# ProPrj__Buck-Boost__V1_2_2026-08-30.net
KiCad netlist of a schematic drawn in EasyEDA Pro
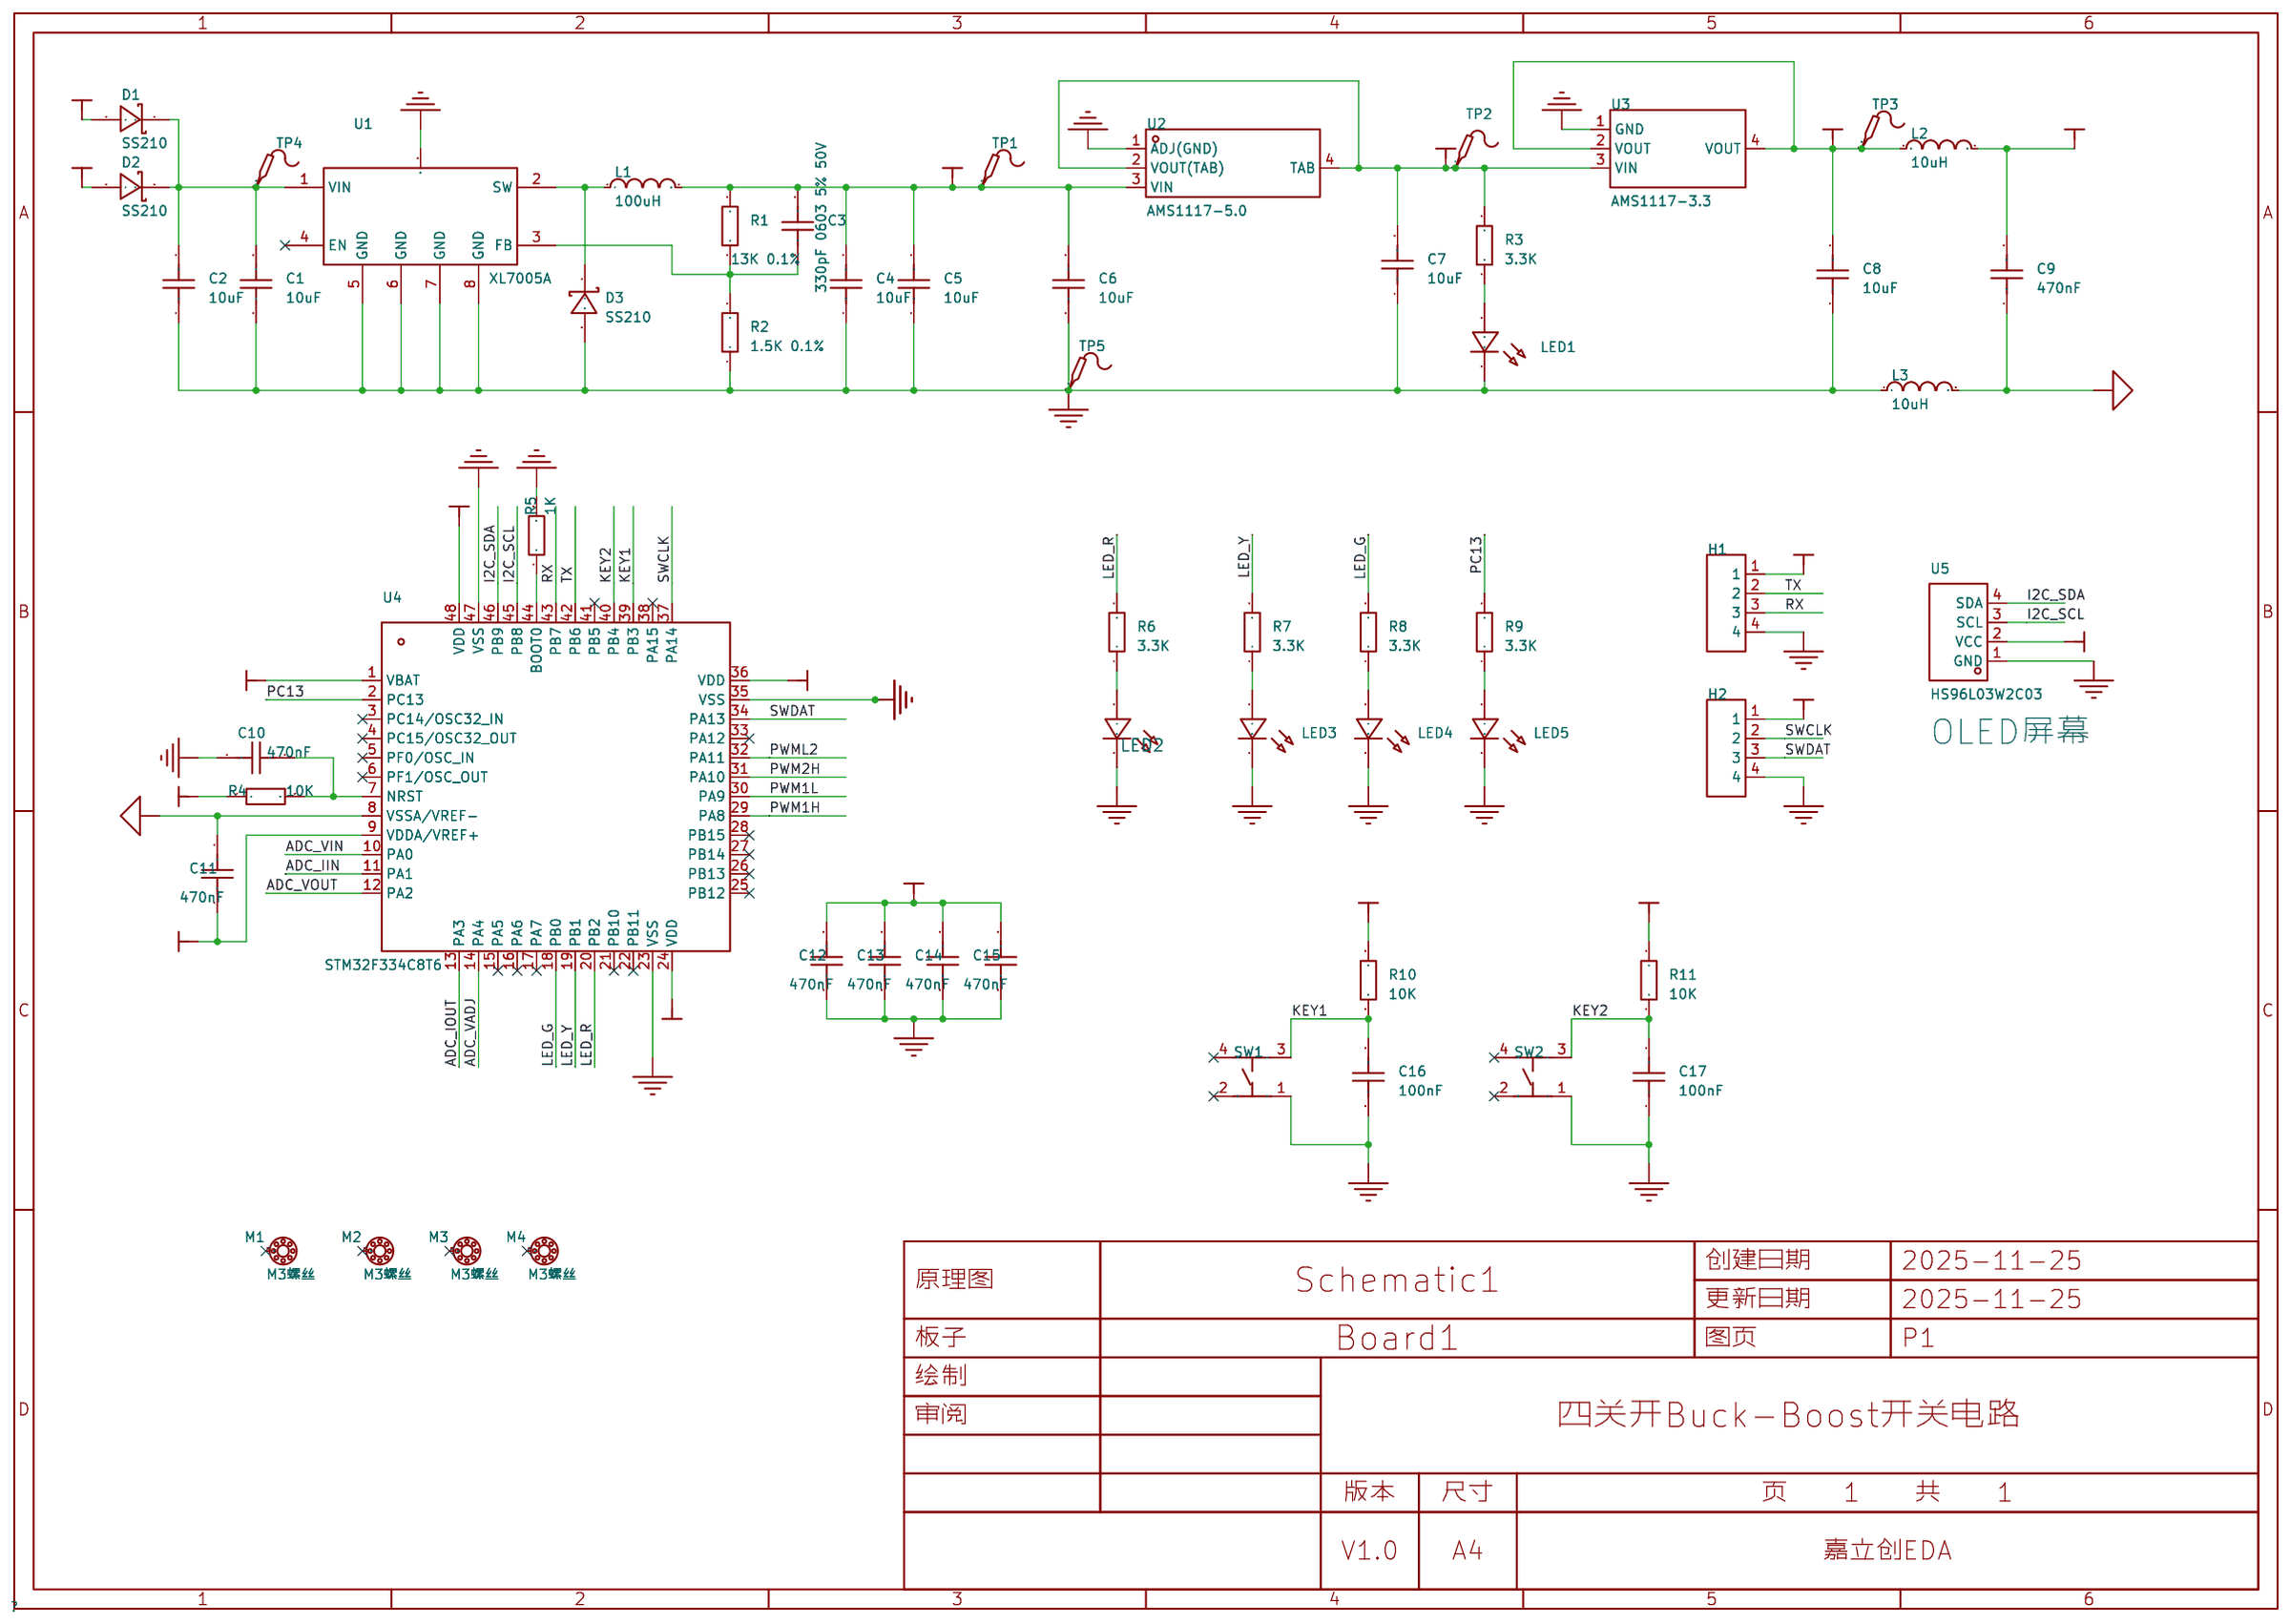
[diagram p0: 辅助电源&主控芯片]
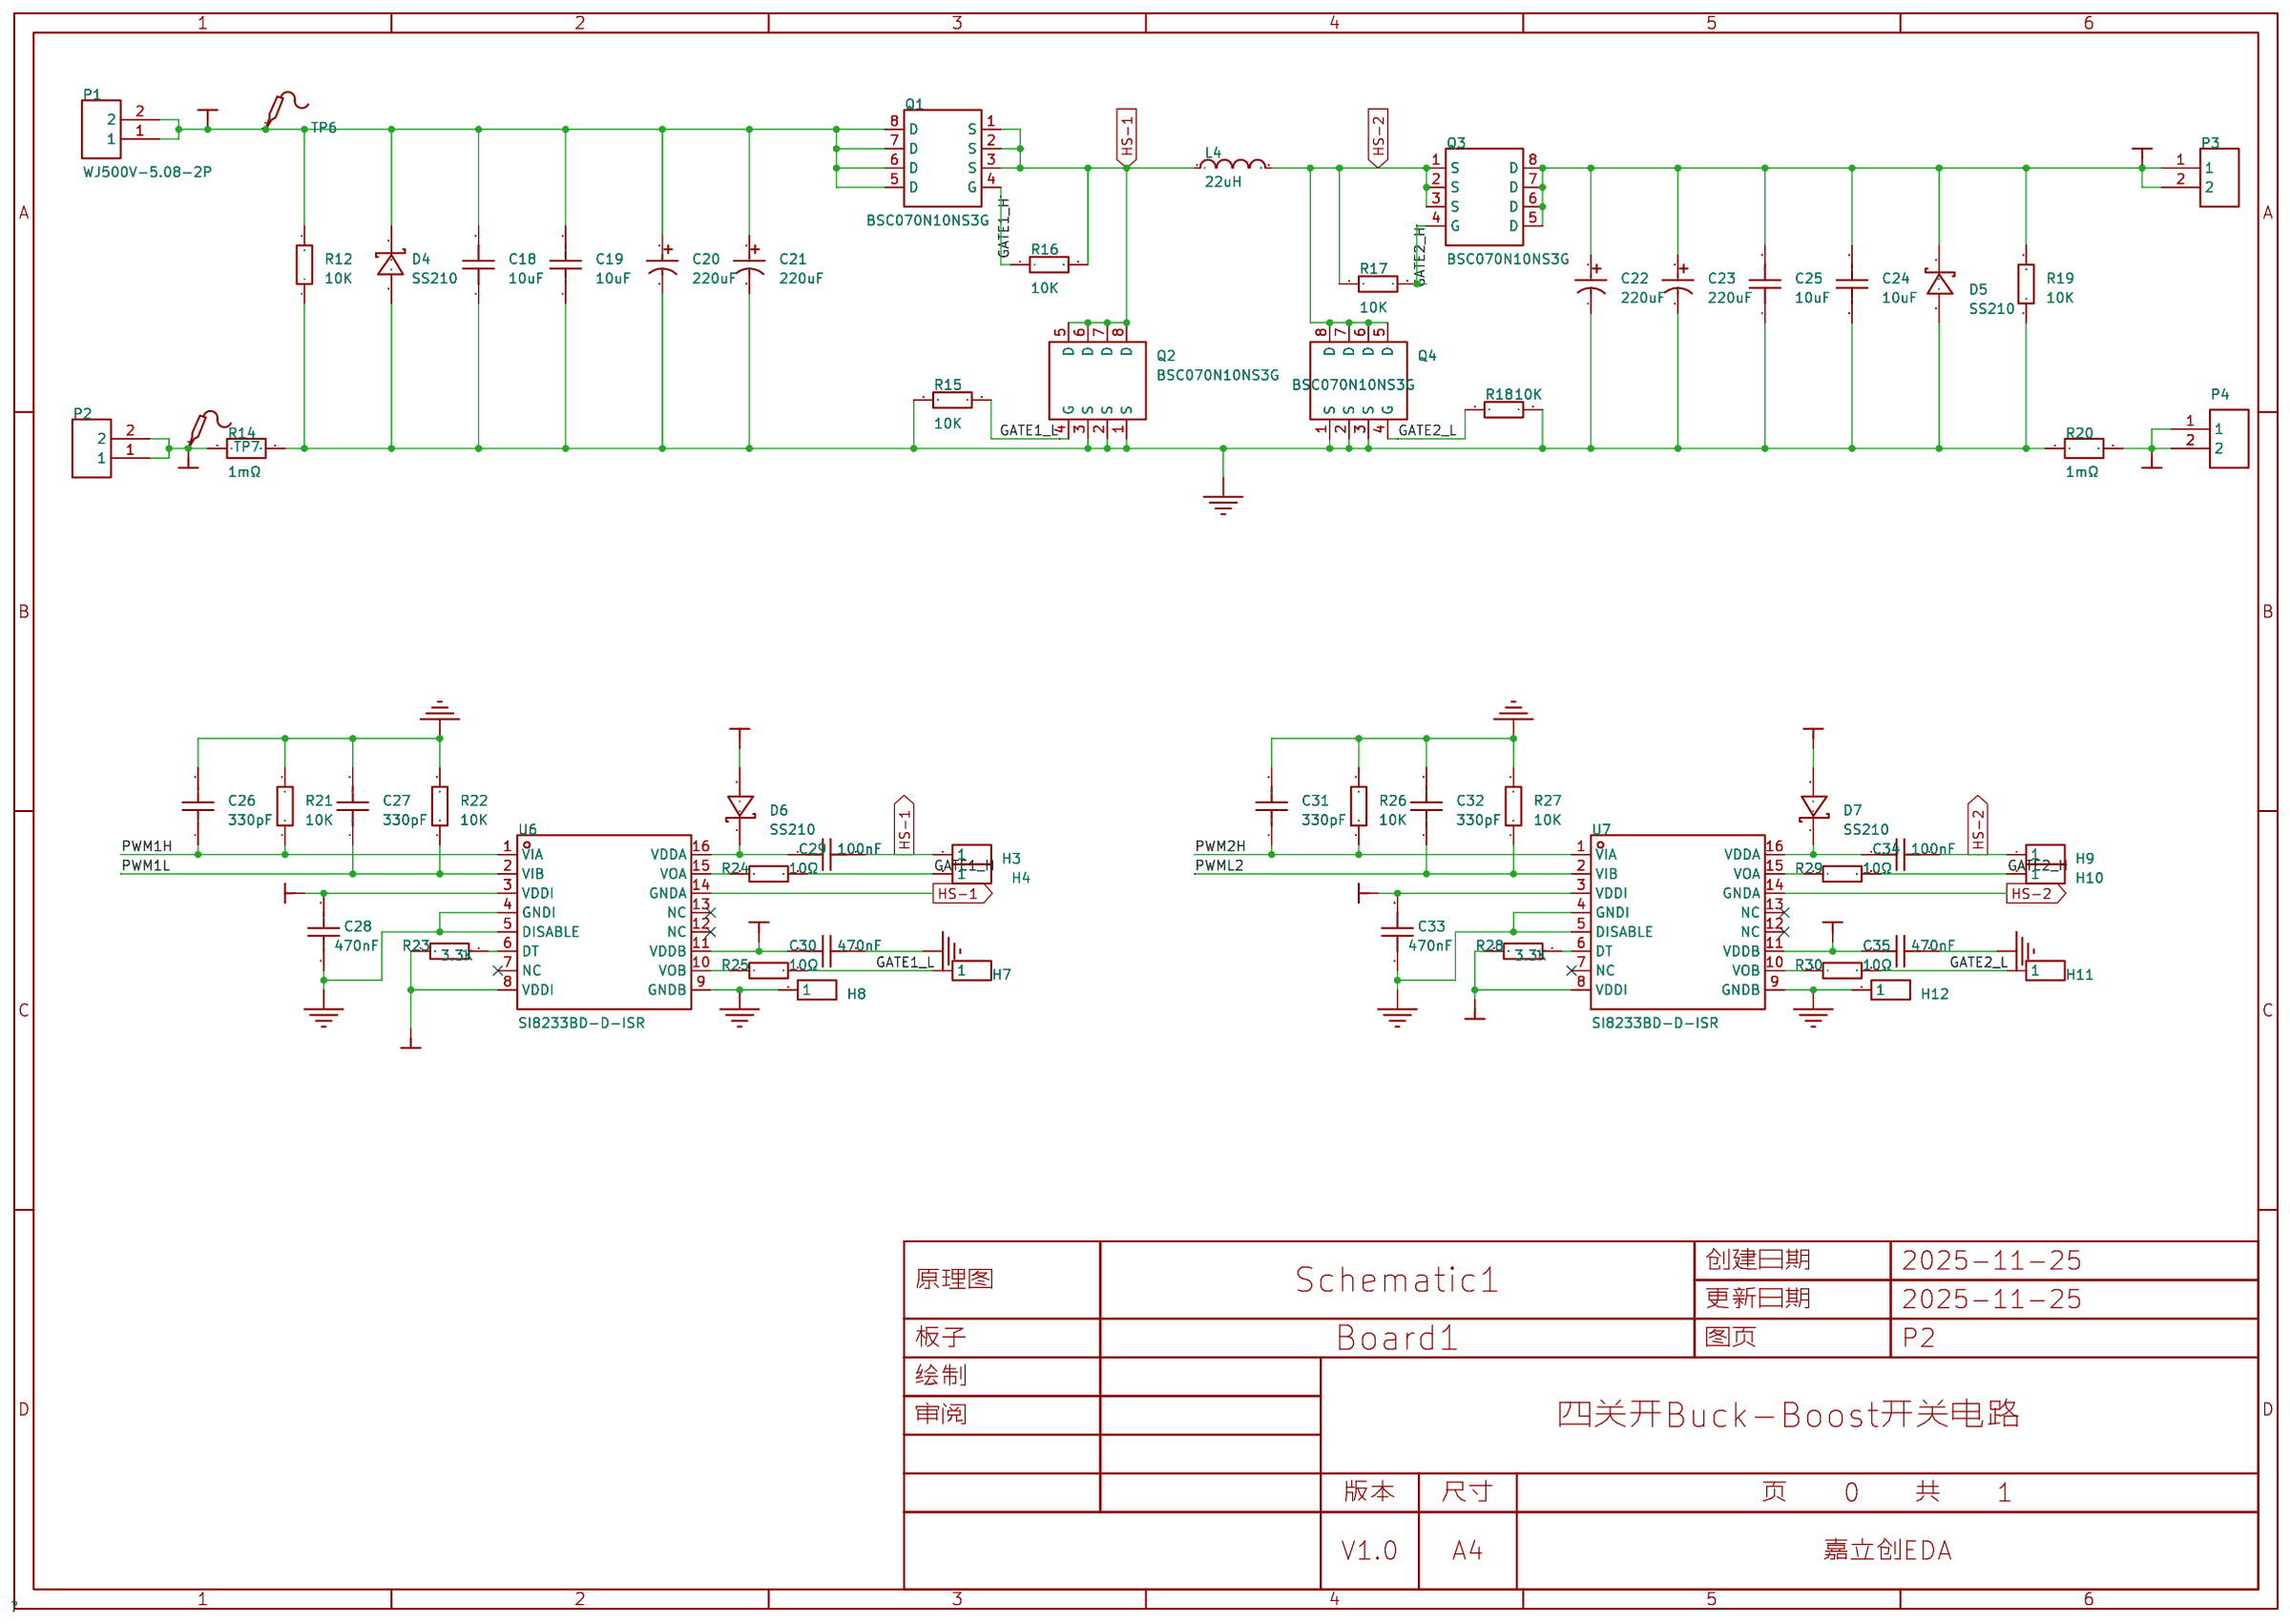
[diagram p1: 主功率&驱动]
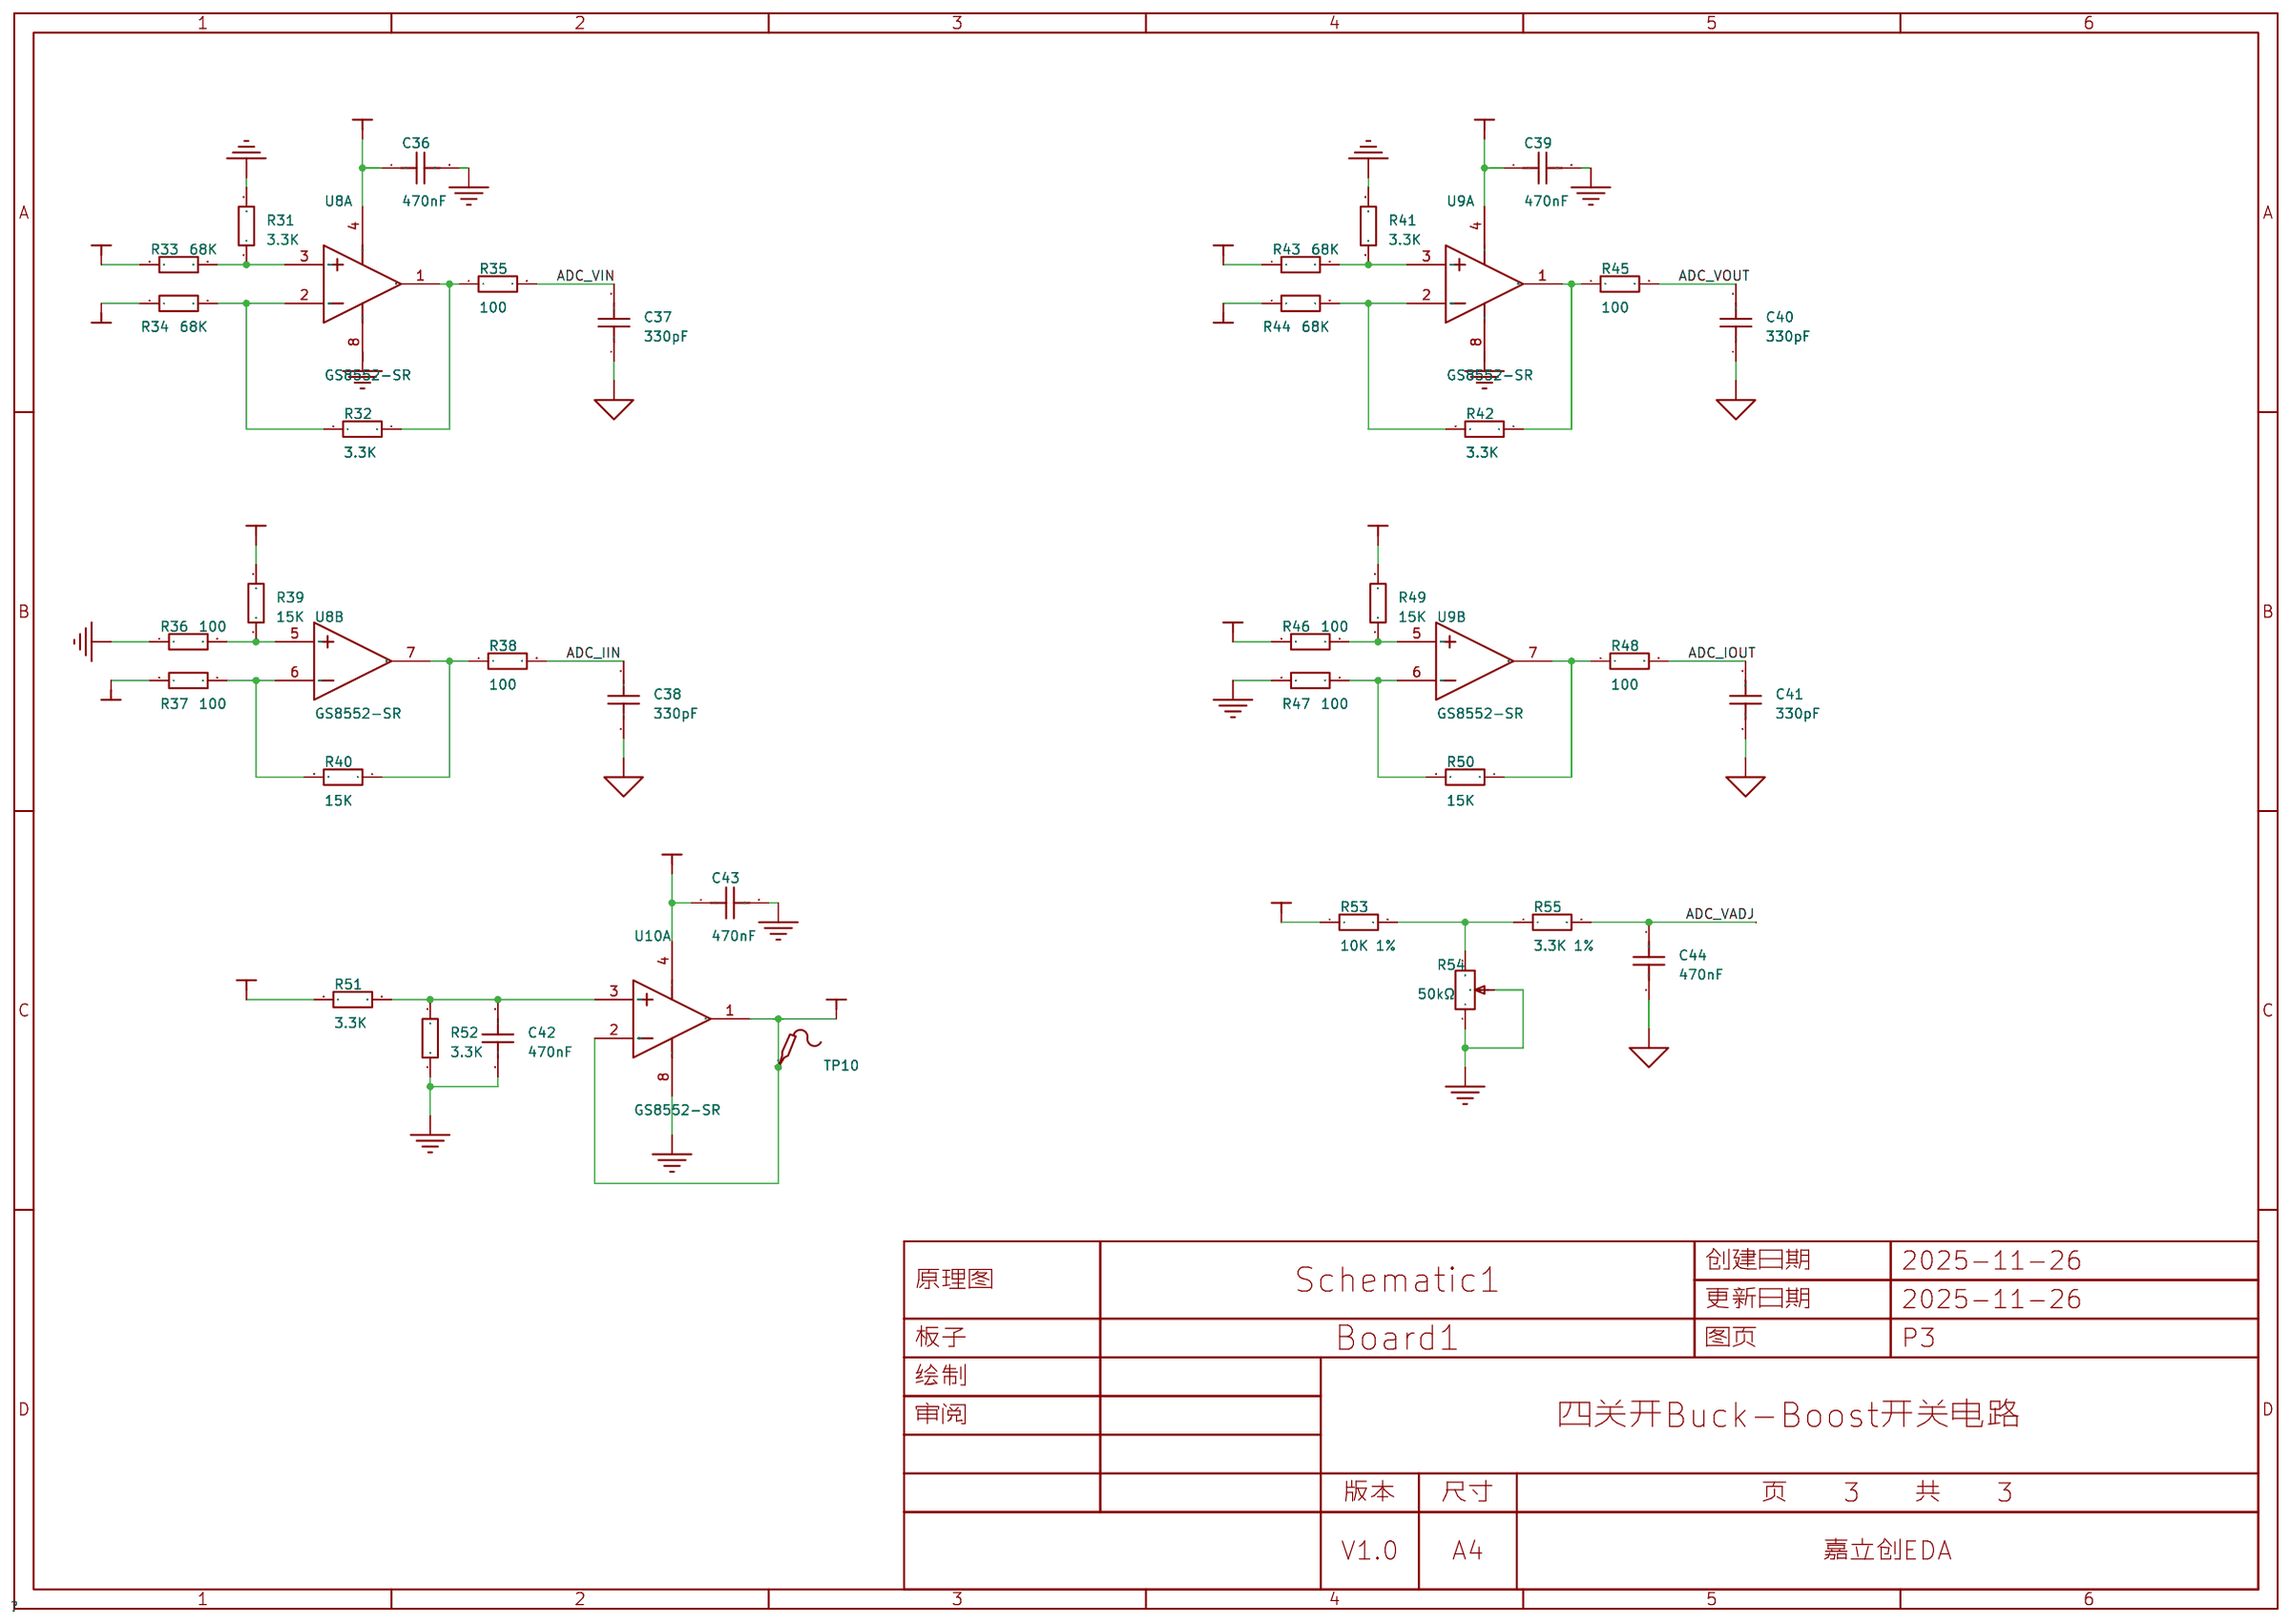
[diagram p2: 信号处理]

(export (version "E")
  (design (tool "Eeschema 10.0.6"))
  (components
    (comp (ref "C1")
      (value "10uF")
      (footprint "easyedapro:C0805")
      (libsource (lib "easyedapro") (part "Capacitance"))
    )
    (comp (ref "C2")
      (value "10uF")
      (footprint "easyedapro:C0805")
      (libsource (lib "easyedapro") (part "Capacitance"))
    )
    (comp (ref "C3")
      (value "330pF 0603 5% 50V")
      (footprint "easyedapro:C0805")
      (libsource (lib "easyedapro") (part "Capacitance"))
    )
    (comp (ref "C4")
      (value "10uF")
      (footprint "easyedapro:C0805")
      (libsource (lib "easyedapro") (part "Capacitance"))
    )
    (comp (ref "C5")
      (value "10uF")
      (footprint "easyedapro:C0805")
      (libsource (lib "easyedapro") (part "Capacitance"))
    )
    (comp (ref "C6")
      (value "10uF")
      (footprint "easyedapro:C0805")
      (libsource (lib "easyedapro") (part "Capacitance"))
    )
    (comp (ref "C7")
      (value "10uF")
      (footprint "easyedapro:C0805")
      (libsource (lib "easyedapro") (part "Capacitance"))
    )
    (comp (ref "C8")
      (value "10uF")
      (footprint "easyedapro:C0805")
      (libsource (lib "easyedapro") (part "Capacitance"))
    )
    (comp (ref "C9")
      (value "470nF")
      (footprint "easyedapro:C0805")
      (libsource (lib "easyedapro") (part "Capacitance"))
    )
    (comp (ref "C10")
      (value "470nF")
      (footprint "easyedapro:C0805")
      (libsource (lib "easyedapro") (part "Capacitance"))
    )
    (comp (ref "C11")
      (value "470nF")
      (footprint "easyedapro:C0805")
      (libsource (lib "easyedapro") (part "Capacitance"))
    )
    (comp (ref "C12")
      (value "470nF")
      (footprint "easyedapro:C0805")
      (libsource (lib "easyedapro") (part "Capacitance"))
    )
    (comp (ref "C13")
      (value "470nF")
      (footprint "easyedapro:C0805")
      (libsource (lib "easyedapro") (part "Capacitance"))
    )
    (comp (ref "C14")
      (value "470nF")
      (footprint "easyedapro:C0805")
      (libsource (lib "easyedapro") (part "Capacitance"))
    )
    (comp (ref "C15")
      (value "470nF")
      (footprint "easyedapro:C0805")
      (libsource (lib "easyedapro") (part "Capacitance"))
    )
    (comp (ref "C16")
      (value "100nF")
      (footprint "easyedapro:C0805")
      (libsource (lib "easyedapro") (part "Capacitance"))
    )
    (comp (ref "C17")
      (value "100nF")
      (footprint "easyedapro:C0805")
      (libsource (lib "easyedapro") (part "Capacitance"))
    )
    (comp (ref "D1")
      (value "SS210")
      (footprint "easyedapro:SMA_L4.4-W2.8-LS5.4-RD")
      (description "正向压降(Vf):850mV@1A;直流反向耐压(Vr):100V;整流电流:2A;")
      (fields (field (name "Manufacturer") "BORN(伯恩半导体)"))
      (libsource (lib "easyedapro") (part "SS210_C306853"))
    )
    (comp (ref "D2")
      (value "SS210")
      (footprint "easyedapro:SMA_L4.4-W2.8-LS5.4-RD")
      (description "正向压降(Vf):850mV@1A;直流反向耐压(Vr):100V;整流电流:2A;")
      (fields (field (name "Manufacturer") "BORN(伯恩半导体)"))
      (libsource (lib "easyedapro") (part "SS210_C306853"))
    )
    (comp (ref "D3")
      (value "SS210")
      (footprint "easyedapro:SMA_L4.4-W2.8-LS5.4-RD")
      (description "正向压降(Vf):850mV@1A;直流反向耐压(Vr):100V;整流电流:2A;")
      (fields (field (name "Manufacturer") "BORN(伯恩半导体)"))
      (libsource (lib "easyedapro") (part "SS210_C306853"))
    )
    (comp (ref "H1")
      (value "~")
      (footprint "easyedapro:HDR-TH_4P-P2.54-V-M")
      (libsource (lib "easyedapro") (part "PZ254V-11-04P"))
    )
    (comp (ref "H2")
      (value "~")
      (footprint "easyedapro:HDR-TH_4P-P2.54-V-M")
      (libsource (lib "easyedapro") (part "PZ254V-11-04P"))
    )
    (comp (ref "L1")
      (value "100uH")
      (footprint "easyedapro:IND-SMD_L6.0-W6.0_FNR60XXS")
      (description "电感值:100uH;精度:±20%;额定电流:880mA;饱和电流(Isat):1A;类型:磁胶屏蔽绕线合金电感;")
      (fields (field (name "Manufacturer Part") "FNR6045S101MT") (field (name "Manufacturer") "cjiang(长江微电)"))
      (libsource (lib "easyedapro") (part "FNR6045S101MT"))
    )
    (comp (ref "L2")
      (value "10uH")
      (footprint "easyedapro:L0603")
      (libsource (lib "easyedapro") (part "SDFL1608S100KTF"))
    )
    (comp (ref "L3")
      (value "10uH")
      (footprint "easyedapro:L0603")
      (libsource (lib "easyedapro") (part "SDFL1608S100KTF"))
    )
    (comp (ref "LED1")
      (value "~")
      (footprint "easyedapro:LED_0603")
      (libsource (lib "easyedapro") (part "LED_G"))
    )
    (comp (ref "LED2")
      (value "~")
      (footprint "easyedapro:LED_0603")
      (libsource (lib "easyedapro") (part "LED_R"))
    )
    (comp (ref "LED3")
      (value "~")
      (footprint "easyedapro:LED_0603")
      (libsource (lib "easyedapro") (part "LED_B"))
    )
    (comp (ref "LED4")
      (value "~")
      (footprint "easyedapro:LED_0603")
      (libsource (lib "easyedapro") (part "LED_G"))
    )
    (comp (ref "LED5")
      (value "~")
      (footprint "easyedapro:LED_0603")
      (libsource (lib "easyedapro") (part "LED_G"))
    )
    (comp (ref "M1") (value "M3螺丝") (footprint "easyedapro:螺钉孔") (libsource (lib "easyedapro") (part "M3螺丝")))
    (comp (ref "M2") (value "M3螺丝") (footprint "easyedapro:螺钉孔") (libsource (lib "easyedapro") (part "M3螺丝")))
    (comp (ref "M3") (value "M3螺丝") (footprint "easyedapro:螺钉孔") (libsource (lib "easyedapro") (part "M3螺丝")))
    (comp (ref "M4") (value "M3螺丝") (footprint "easyedapro:螺钉孔") (libsource (lib "easyedapro") (part "M3螺丝")))
    (comp (ref "R1")
      (value "13K 0.1%")
      (footprint "easyedapro:R0603")
      (libsource (lib "easyedapro") (part "电阻"))
    )
    (comp (ref "R2")
      (value "1.5K 0.1%")
      (footprint "easyedapro:R0603")
      (libsource (lib "easyedapro") (part "电阻"))
    )
    (comp (ref "R3") (value "3.3K") (footprint "easyedapro:R0603") (libsource (lib "easyedapro") (part "电阻")))
    (comp (ref "R4") (value "10K") (footprint "easyedapro:R0603") (libsource (lib "easyedapro") (part "电阻")))
    (comp (ref "R5") (value "1K") (footprint "easyedapro:R0603") (libsource (lib "easyedapro") (part "电阻")))
    (comp (ref "R6") (value "3.3K") (footprint "easyedapro:R0603") (libsource (lib "easyedapro") (part "电阻")))
    (comp (ref "R7") (value "3.3K") (footprint "easyedapro:R0603") (libsource (lib "easyedapro") (part "电阻")))
    (comp (ref "R8") (value "3.3K") (footprint "easyedapro:R0603") (libsource (lib "easyedapro") (part "电阻")))
    (comp (ref "R9") (value "3.3K") (footprint "easyedapro:R0603") (libsource (lib "easyedapro") (part "电阻")))
    (comp (ref "R10") (value "10K") (footprint "easyedapro:R0603") (libsource (lib "easyedapro") (part "电阻")))
    (comp (ref "R11") (value "10K") (footprint "easyedapro:R0603") (libsource (lib "easyedapro") (part "电阻")))
    (comp (ref "SW1")
      (value "KH-6X6X5H-STM")
      (footprint "easyedapro:SW-SMD_4P-L6.0-W6.0-P4.50-LS9.0_H5.0")
      (fields (field (name "Manufacturer") "kinghelm(金航标)"))
      (libsource (lib "easyedapro") (part "KH-6X6X5H-STM"))
    )
    (comp (ref "SW2")
      (value "KH-6X6X5H-STM")
      (footprint "easyedapro:SW-SMD_4P-L6.0-W6.0-P4.50-LS9.0_H5.0")
      (fields (field (name "Manufacturer") "kinghelm(金航标)"))
      (libsource (lib "easyedapro") (part "KH-6X6X5H-STM"))
    )
    (comp (ref "TP1")
      (value "~")
      (footprint "easyedapro:Test-Point-0.5mm")
      (description "Test Point 测试点")
      (libsource (lib "easyedapro") (part "Test-Point"))
    )
    (comp (ref "TP2")
      (value "~")
      (footprint "easyedapro:Test-Point-0.5mm")
      (description "Test Point 测试点")
      (libsource (lib "easyedapro") (part "Test-Point"))
    )
    (comp (ref "TP3")
      (value "~")
      (footprint "easyedapro:Test-Point-0.5mm")
      (description "Test Point 测试点")
      (libsource (lib "easyedapro") (part "Test-Point"))
    )
    (comp (ref "TP4")
      (value "~")
      (footprint "easyedapro:Test-Point-0.5mm")
      (description "Test Point 测试点")
      (libsource (lib "easyedapro") (part "Test-Point"))
    )
    (comp (ref "TP5")
      (value "~")
      (footprint "easyedapro:Test-Point-0.5mm")
      (description "Test Point 测试点")
      (libsource (lib "easyedapro") (part "Test-Point"))
    )
    (comp (ref "U1")
      (value "XL7005A")
      (footprint "easyedapro:SOIC-8_L4.9-W3.9-P1.27-LS6.0-BL-EP3.1-1")
      (description "功能类型:降压型;工作电压:5V~80V;输出电压:1.25V~20V;输出电流:400mA;输出类型:可调;")
      (fields (field (name "Manufacturer") "XLSEMI(芯龙)"))
      (libsource (lib "easyedapro") (part "XL7005A"))
    )
    (comp (ref "U2")
      (value "AMS1117-5.0")
      (footprint "easyedapro:SOT-223_L6.7-W3.5-P2.30-BR")
      (description "输出类型:固定;工作电压:18V;输出电压:5V;输出电流:1A;电源纹波抑制比(PSRR):60dB@(120Hz);输出极性:正极;")
      (fields (field (name "Manufacturer") "UMW(友台半导体)"))
      (libsource (lib "easyedapro") (part "AMS1117-5.0_C347223"))
    )
    (comp (ref "U3")
      (value "AMS1117-3.3")
      (footprint "easyedapro:SOT-223-3_L6.5-W3.4-P2.30-LS7.0-BR")
      (description "输出类型:固定;工作电压:16V;输出电压:3.3V;输出电流:1A;电源纹波抑制比(PSRR):72dB@(120Hz);输出极性:正极;")
      (fields (field (name "Manufacturer") "AMS"))
      (libsource (lib "easyedapro") (part "AMS1117-3.3"))
    )
    (comp (ref "U4")
      (value "STM32F334C8T6")
      (footprint "easyedapro:LQFP-48_L7.0-W7.0-P0.50-LS9.0-BL")
      (description "CPU内核:ARM-M4;CPU最大主频:72MHz;应用领域:-;")
      (fields (field (name "Manufacturer") "ST(意法半导体)"))
      (libsource (lib "easyedapro") (part "STM32F334C8T6"))
    )
    (comp (ref "U5")
      (value "HS96L03W2C03")
      (footprint "easyedapro:OLED-TH_L27.8-W27.2-P2.54_C9900033791")
      (fields (field (name "Manufacturer") "HS(汉昇)"))
      (libsource (lib "easyedapro") (part "HS96L03W2C03"))
    )
    (comp (ref "C18")
      (value "10uF")
      (footprint "easyedapro:C0805")
      (libsource (lib "easyedapro") (part "Capacitance"))
    )
    (comp (ref "C19")
      (value "10uF")
      (footprint "easyedapro:C0805")
      (libsource (lib "easyedapro") (part "Capacitance"))
    )
    (comp (ref "C20")
      (value "220uF")
      (footprint "easyedapro:CAP-TH_BD10.0-P5.00-D1.0-FD")
      (fields
        (field (name "Manufacturer Part") "GR227M063G17RR0VL4FP0")
        (field (name "Manufacturer") "Chengx(承兴)")
      )
      (libsource (lib "easyedapro") (part "220uf/63V"))
    )
    (comp (ref "C21")
      (value "220uF")
      (footprint "easyedapro:CAP-TH_BD10.0-P5.00-D1.0-FD")
      (fields
        (field (name "Manufacturer Part") "GR227M063G17RR0VL4FP0")
        (field (name "Manufacturer") "Chengx(承兴)")
      )
      (libsource (lib "easyedapro") (part "220uf/63V"))
    )
    (comp (ref "C22")
      (value "220uF")
      (footprint "easyedapro:CAP-TH_BD10.0-P5.00-D1.0-FD")
      (fields
        (field (name "Manufacturer Part") "GR227M063G17RR0VL4FP0")
        (field (name "Manufacturer") "Chengx(承兴)")
      )
      (libsource (lib "easyedapro") (part "220uf/63V"))
    )
    (comp (ref "C23")
      (value "220uF")
      (footprint "easyedapro:CAP-TH_BD10.0-P5.00-D1.0-FD")
      (fields
        (field (name "Manufacturer Part") "GR227M063G17RR0VL4FP0")
        (field (name "Manufacturer") "Chengx(承兴)")
      )
      (libsource (lib "easyedapro") (part "220uf/63V"))
    )
    (comp (ref "C24")
      (value "10uF")
      (footprint "easyedapro:C0805")
      (libsource (lib "easyedapro") (part "Capacitance"))
    )
    (comp (ref "C25")
      (value "10uF")
      (footprint "easyedapro:C0805")
      (libsource (lib "easyedapro") (part "Capacitance"))
    )
    (comp (ref "C26")
      (value "330pF")
      (footprint "easyedapro:C0805")
      (libsource (lib "easyedapro") (part "Capacitance"))
    )
    (comp (ref "C27")
      (value "330pF")
      (footprint "easyedapro:C0805")
      (libsource (lib "easyedapro") (part "Capacitance"))
    )
    (comp (ref "C28")
      (value "470nF")
      (footprint "easyedapro:C0805")
      (libsource (lib "easyedapro") (part "Capacitance"))
    )
    (comp (ref "C29")
      (value "100nF")
      (footprint "easyedapro:C0805")
      (libsource (lib "easyedapro") (part "Capacitance"))
    )
    (comp (ref "C30")
      (value "470nF")
      (footprint "easyedapro:C0805")
      (libsource (lib "easyedapro") (part "Capacitance"))
    )
    (comp (ref "C31")
      (value "330pF")
      (footprint "easyedapro:C0805")
      (libsource (lib "easyedapro") (part "Capacitance"))
    )
    (comp (ref "C32")
      (value "330pF")
      (footprint "easyedapro:C0805")
      (libsource (lib "easyedapro") (part "Capacitance"))
    )
    (comp (ref "C33")
      (value "470nF")
      (footprint "easyedapro:C0805")
      (libsource (lib "easyedapro") (part "Capacitance"))
    )
    (comp (ref "C34")
      (value "100nF")
      (footprint "easyedapro:C0805")
      (libsource (lib "easyedapro") (part "Capacitance"))
    )
    (comp (ref "C35")
      (value "470nF")
      (footprint "easyedapro:C0805")
      (libsource (lib "easyedapro") (part "Capacitance"))
    )
    (comp (ref "D4")
      (value "SS210")
      (footprint "easyedapro:SMA_L4.4-W2.8-LS5.4-RD")
      (description "正向压降(Vf):850mV@1A;直流反向耐压(Vr):100V;整流电流:2A;")
      (fields (field (name "Manufacturer") "BORN(伯恩半导体)"))
      (libsource (lib "easyedapro") (part "SS210_C306853"))
    )
    (comp (ref "D5")
      (value "SS210")
      (footprint "easyedapro:SMA_L4.4-W2.8-LS5.4-RD")
      (description "正向压降(Vf):850mV@1A;直流反向耐压(Vr):100V;整流电流:2A;")
      (fields (field (name "Manufacturer") "BORN(伯恩半导体)"))
      (libsource (lib "easyedapro") (part "SS210_C306853"))
    )
    (comp (ref "D6")
      (value "SS210")
      (footprint "easyedapro:SMA_L4.4-W2.8-LS5.4-RD")
      (description "正向压降(Vf):850mV@1A;直流反向耐压(Vr):100V;整流电流:2A;")
      (fields (field (name "Manufacturer") "BORN(伯恩半导体)"))
      (libsource (lib "easyedapro") (part "SS210_C306853"))
    )
    (comp (ref "D7")
      (value "SS210")
      (footprint "easyedapro:SMA_L4.4-W2.8-LS5.4-RD")
      (description "正向压降(Vf):850mV@1A;直流反向耐压(Vr):100V;整流电流:2A;")
      (fields (field (name "Manufacturer") "BORN(伯恩半导体)"))
      (libsource (lib "easyedapro") (part "SS210_C306853"))
    )
    (comp (ref "H3")
      (value "~")
      (footprint "easyedapro:HDR-TH_1P-V-M_XKB_X4611WV-01I-C28D40")
      (libsource (lib "easyedapro") (part "HDR_1x1"))
    )
    (comp (ref "H4")
      (value "~")
      (footprint "easyedapro:HDR-TH_1P-V-M_XKB_X4611WV-01I-C28D40")
      (libsource (lib "easyedapro") (part "HDR_1x1"))
    )
    (comp (ref "H7")
      (value "~")
      (footprint "easyedapro:HDR-TH_1P-V-M_XKB_X4611WV-01I-C28D40")
      (libsource (lib "easyedapro") (part "HDR_1x1"))
    )
    (comp (ref "H8")
      (value "~")
      (footprint "easyedapro:HDR-TH_1P-V-M_XKB_X4611WV-01I-C28D40")
      (libsource (lib "easyedapro") (part "HDR_1x1"))
    )
    (comp (ref "H9")
      (value "~")
      (footprint "easyedapro:HDR-TH_1P-V-M_XKB_X4611WV-01I-C28D40")
      (libsource (lib "easyedapro") (part "HDR_1x1"))
    )
    (comp (ref "H10")
      (value "~")
      (footprint "easyedapro:HDR-TH_1P-V-M_XKB_X4611WV-01I-C28D40")
      (libsource (lib "easyedapro") (part "HDR_1x1"))
    )
    (comp (ref "H11")
      (value "~")
      (footprint "easyedapro:HDR-TH_1P-V-M_XKB_X4611WV-01I-C28D40")
      (libsource (lib "easyedapro") (part "HDR_1x1"))
    )
    (comp (ref "H12")
      (value "~")
      (footprint "easyedapro:HDR-TH_1P-V-M_XKB_X4611WV-01I-C28D40")
      (libsource (lib "easyedapro") (part "HDR_1x1"))
    )
    (comp (ref "L4")
      (value "22uH")
      (footprint "easyedapro:IND-SMD_L17.5-W17.0_YXMAC1770")
      (fields
        (field (name "Manufacturer Part") "TMPA1707SP-220MN-D")
        (field (name "Manufacturer") "TAI-TECH(台庆)")
      )
      (libsource (lib "easyedapro") (part "TMPA1707SP-220MN-D"))
    )
    (comp (ref "P1")
      (value "WJ500V-5.08-2P")
      (footprint "easyedapro:CONN-TH_2P-P5.00_WJ500V-5.08-2P")
      (fields (field (name "Manufacturer") "KANGNEX(康奈克斯电气)"))
      (libsource (lib "easyedapro") (part "WJ500V-5.08-2P-14-00A"))
    )
    (comp (ref "P2")
      (value "WJ500V-5.08-2P")
      (footprint "easyedapro:CONN-TH_2P-P5.00_WJ500V-5.08-2P")
      (fields (field (name "Manufacturer") "KANGNEX(康奈克斯电气)"))
      (libsource (lib "easyedapro") (part "WJ500V-5.08-2P-14-00A"))
    )
    (comp (ref "P3")
      (value "WJ500V-5.08-2P")
      (footprint "easyedapro:CONN-TH_2P-P5.00_WJ500V-5.08-2P")
      (fields (field (name "Manufacturer") "KANGNEX(康奈克斯电气)"))
      (libsource (lib "easyedapro") (part "WJ500V-5.08-2P-14-00A"))
    )
    (comp (ref "P4")
      (value "WJ500V-5.08-2P")
      (footprint "easyedapro:CONN-TH_2P-P5.00_WJ500V-5.08-2P")
      (fields (field (name "Manufacturer") "KANGNEX(康奈克斯电气)"))
      (libsource (lib "easyedapro") (part "WJ500V-5.08-2P-14-00A"))
    )
    (comp (ref "Q1")
      (value "BSC070N10NS3G")
      (footprint "easyedapro:PG-TDSON-8_L5.0-W6.0-P1.27-BL-EP")
      (fields (field (name "Manufacturer") "Infineon(英飞凌)"))
      (libsource (lib "easyedapro") (part "BSC070N10NS3G"))
    )
    (comp (ref "Q2")
      (value "BSC070N10NS3G")
      (footprint "easyedapro:PG-TDSON-8_L5.0-W6.0-P1.27-BL-EP")
      (fields (field (name "Manufacturer") "Infineon(英飞凌)"))
      (libsource (lib "easyedapro") (part "BSC070N10NS3G"))
    )
    (comp (ref "Q3")
      (value "BSC070N10NS3G")
      (footprint "easyedapro:PG-TDSON-8_L5.0-W6.0-P1.27-BL-EP")
      (fields (field (name "Manufacturer") "Infineon(英飞凌)"))
      (libsource (lib "easyedapro") (part "BSC070N10NS3G"))
    )
    (comp (ref "Q4")
      (value "BSC070N10NS3G")
      (footprint "easyedapro:PG-TDSON-8_L5.0-W6.0-P1.27-BL-EP")
      (fields (field (name "Manufacturer") "Infineon(英飞凌)"))
      (libsource (lib "easyedapro") (part "BSC070N10NS3G"))
    )
    (comp (ref "R12") (value "10K") (footprint "easyedapro:R0603") (libsource (lib "easyedapro") (part "电阻")))
    (comp (ref "R14")
      (value "1mΩ")
      (footprint "easyedapro:RES-SMD_L6.3-W3.2_R2512")
      (fields (field (name "Manufacturer Part") "RE2512F3R001") (field (name "Manufacturer") "JIERR(捷而瑞)"))
      (libsource (lib "easyedapro") (part "RE2512F3R001"))
    )
    (comp (ref "R15") (value "10K") (footprint "easyedapro:R0603") (libsource (lib "easyedapro") (part "电阻")))
    (comp (ref "R16") (value "10K") (footprint "easyedapro:R0603") (libsource (lib "easyedapro") (part "电阻")))
    (comp (ref "R17") (value "10K") (footprint "easyedapro:R0603") (libsource (lib "easyedapro") (part "电阻")))
    (comp (ref "R18") (value "10K") (footprint "easyedapro:R0603") (libsource (lib "easyedapro") (part "电阻")))
    (comp (ref "R19") (value "10K") (footprint "easyedapro:R0603") (libsource (lib "easyedapro") (part "电阻")))
    (comp (ref "R20")
      (value "1mΩ")
      (footprint "easyedapro:RES-SMD_L6.3-W3.2_R2512")
      (fields (field (name "Manufacturer Part") "RE2512F3R001") (field (name "Manufacturer") "JIERR(捷而瑞)"))
      (libsource (lib "easyedapro") (part "RE2512F3R001"))
    )
    (comp (ref "R21") (value "10K") (footprint "easyedapro:R0603") (libsource (lib "easyedapro") (part "电阻")))
    (comp (ref "R22") (value "10K") (footprint "easyedapro:R0603") (libsource (lib "easyedapro") (part "电阻")))
    (comp (ref "R23")
      (value "3.3K")
      (footprint "easyedapro:R0603")
      (libsource (lib "easyedapro") (part "电阻"))
    )
    (comp (ref "R24") (value "10Ω") (footprint "easyedapro:R0603") (libsource (lib "easyedapro") (part "电阻")))
    (comp (ref "R25") (value "10Ω") (footprint "easyedapro:R0603") (libsource (lib "easyedapro") (part "电阻")))
    (comp (ref "R26") (value "10K") (footprint "easyedapro:R0603") (libsource (lib "easyedapro") (part "电阻")))
    (comp (ref "R27") (value "10K") (footprint "easyedapro:R0603") (libsource (lib "easyedapro") (part "电阻")))
    (comp (ref "R28")
      (value "3.3K")
      (footprint "easyedapro:R0603")
      (libsource (lib "easyedapro") (part "电阻"))
    )
    (comp (ref "R29") (value "10Ω") (footprint "easyedapro:R0603") (libsource (lib "easyedapro") (part "电阻")))
    (comp (ref "R30") (value "10Ω") (footprint "easyedapro:R0603") (libsource (lib "easyedapro") (part "电阻")))
    (comp (ref "TP6")
      (value "~")
      (footprint "easyedapro:Test-Point-0.5mm")
      (description "Test Point 测试点")
      (libsource (lib "easyedapro") (part "Test-Point"))
    )
    (comp (ref "TP7")
      (value "~")
      (footprint "easyedapro:Test-Point-0.5mm")
      (description "Test Point 测试点")
      (libsource (lib "easyedapro") (part "Test-Point"))
    )
    (comp (ref "U6")
      (value "SI8233BD-D-ISR")
      (footprint "easyedapro:SOIC-16_L10.3-W7.5-P1.27-LS10.3-BL")
      (fields (field (name "Manufacturer") "SKYWORKS/SILICON LABS(芯科)"))
      (libsource (lib "easyedapro") (part "SI8233BD-D-ISR"))
    )
    (comp (ref "U7")
      (value "SI8233BD-D-ISR")
      (footprint "easyedapro:SOIC-16_L10.3-W7.5-P1.27-LS10.3-BL")
      (fields (field (name "Manufacturer") "SKYWORKS/SILICON LABS(芯科)"))
      (libsource (lib "easyedapro") (part "SI8233BD-D-ISR"))
    )
    (comp (ref "C36")
      (value "470nF")
      (footprint "easyedapro:C0805")
      (libsource (lib "easyedapro") (part "Capacitance"))
    )
    (comp (ref "C37")
      (value "330pF")
      (footprint "easyedapro:C0805")
      (libsource (lib "easyedapro") (part "Capacitance"))
    )
    (comp (ref "C38")
      (value "330pF")
      (footprint "easyedapro:C0805")
      (libsource (lib "easyedapro") (part "Capacitance"))
    )
    (comp (ref "C39")
      (value "470nF")
      (footprint "easyedapro:C0805")
      (libsource (lib "easyedapro") (part "Capacitance"))
    )
    (comp (ref "C40")
      (value "330pF")
      (footprint "easyedapro:C0805")
      (libsource (lib "easyedapro") (part "Capacitance"))
    )
    (comp (ref "C41")
      (value "330pF")
      (footprint "easyedapro:C0805")
      (libsource (lib "easyedapro") (part "Capacitance"))
    )
    (comp (ref "C42")
      (value "470nF")
      (footprint "easyedapro:C0805")
      (libsource (lib "easyedapro") (part "Capacitance"))
    )
    (comp (ref "C43")
      (value "470nF")
      (footprint "easyedapro:C0805")
      (libsource (lib "easyedapro") (part "Capacitance"))
    )
    (comp (ref "C44")
      (value "470nF")
      (footprint "easyedapro:C0805")
      (libsource (lib "easyedapro") (part "Capacitance"))
    )
    (comp (ref "R31")
      (value "3.3K")
      (footprint "easyedapro:R0603")
      (libsource (lib "easyedapro") (part "电阻"))
    )
    (comp (ref "R32")
      (value "3.3K")
      (footprint "easyedapro:R0603")
      (libsource (lib "easyedapro") (part "电阻"))
    )
    (comp (ref "R33") (value "68K") (footprint "easyedapro:R0603") (libsource (lib "easyedapro") (part "电阻")))
    (comp (ref "R34") (value "68K") (footprint "easyedapro:R0603") (libsource (lib "easyedapro") (part "电阻")))
    (comp (ref "R35") (value "100") (footprint "easyedapro:R0603") (libsource (lib "easyedapro") (part "电阻")))
    (comp (ref "R36") (value "100") (footprint "easyedapro:R0603") (libsource (lib "easyedapro") (part "电阻")))
    (comp (ref "R37") (value "100") (footprint "easyedapro:R0603") (libsource (lib "easyedapro") (part "电阻")))
    (comp (ref "R38") (value "100") (footprint "easyedapro:R0603") (libsource (lib "easyedapro") (part "电阻")))
    (comp (ref "R39") (value "15K") (footprint "easyedapro:R0603") (libsource (lib "easyedapro") (part "电阻")))
    (comp (ref "R40") (value "15K") (footprint "easyedapro:R0603") (libsource (lib "easyedapro") (part "电阻")))
    (comp (ref "R41")
      (value "3.3K")
      (footprint "easyedapro:R0603")
      (libsource (lib "easyedapro") (part "电阻"))
    )
    (comp (ref "R42")
      (value "3.3K")
      (footprint "easyedapro:R0603")
      (libsource (lib "easyedapro") (part "电阻"))
    )
    (comp (ref "R43") (value "68K") (footprint "easyedapro:R0603") (libsource (lib "easyedapro") (part "电阻")))
    (comp (ref "R44") (value "68K") (footprint "easyedapro:R0603") (libsource (lib "easyedapro") (part "电阻")))
    (comp (ref "R45") (value "100") (footprint "easyedapro:R0603") (libsource (lib "easyedapro") (part "电阻")))
    (comp (ref "R46") (value "100") (footprint "easyedapro:R0603") (libsource (lib "easyedapro") (part "电阻")))
    (comp (ref "R47") (value "100") (footprint "easyedapro:R0603") (libsource (lib "easyedapro") (part "电阻")))
    (comp (ref "R48") (value "100") (footprint "easyedapro:R0603") (libsource (lib "easyedapro") (part "电阻")))
    (comp (ref "R49") (value "15K") (footprint "easyedapro:R0603") (libsource (lib "easyedapro") (part "电阻")))
    (comp (ref "R50") (value "15K") (footprint "easyedapro:R0603") (libsource (lib "easyedapro") (part "电阻")))
    (comp (ref "R51")
      (value "3.3K")
      (footprint "easyedapro:R0603")
      (libsource (lib "easyedapro") (part "电阻"))
    )
    (comp (ref "R52")
      (value "3.3K")
      (footprint "easyedapro:R0603")
      (libsource (lib "easyedapro") (part "电阻"))
    )
    (comp (ref "R53")
      (value "10K 1%")
      (footprint "easyedapro:R0603")
      (libsource (lib "easyedapro") (part "电阻"))
    )
    (comp (ref "R54")
      (value "50kΩ")
      (footprint "easyedapro:RES-ADJ-TH_3296W")
      (fields (field (name "Manufacturer Part") "3296W-1-503LF") (field (name "Manufacturer") "JIERR(捷而瑞)"))
      (libsource (lib "easyedapro") (part "3296W-1-503LF_C49190466"))
    )
    (comp (ref "R55")
      (value "3.3K 1%")
      (footprint "easyedapro:R0603")
      (libsource (lib "easyedapro") (part "电阻"))
    )
    (comp (ref "TP10")
      (value "~")
      (footprint "easyedapro:Test-Point-0.5mm")
      (description "Test Point 测试点")
      (libsource (lib "easyedapro") (part "Test-Point"))
    )
    (comp (ref "U8")
      (value "GS8552-SR")
      (footprint "easyedapro:SOIC-8_L4.9-W3.9-P1.27-LS6.0-BL")
      (fields (field (name "Manufacturer") "Gainsil(聚洵)"))
      (libsource (lib "easyedapro") (part "GS8552-SR"))
    )
    (comp (ref "U9")
      (value "GS8552-SR")
      (footprint "easyedapro:SOIC-8_L4.9-W3.9-P1.27-LS6.0-BL")
      (fields (field (name "Manufacturer") "Gainsil(聚洵)"))
      (libsource (lib "easyedapro") (part "GS8552-SR"))
    )
    (comp (ref "U10")
      (value "GS8552-SR")
      (footprint "easyedapro:SOIC-8_L4.9-W3.9-P1.27-LS6.0-BL")
      (fields (field (name "Manufacturer") "Gainsil(聚洵)"))
      (libsource (lib "easyedapro") (part "GS8552-SR"))
    )
  )
  (nets
    (net (code "1") (name "+5V") (class "Default")
      (node (ref "C28") (pin "2") (pinfunction "2_2") (pintype "input"))
      (node (ref "C33") (pin "2") (pinfunction "2_2") (pintype "input"))
      (node (ref "C36") (pin "1") (pinfunction "1_1") (pintype "input"))
      (node (ref "C39") (pin "1") (pinfunction "1_1") (pintype "input"))
      (node (ref "C43") (pin "1") (pinfunction "1_1") (pintype "input"))
      (node (ref "C7") (pin "2") (pinfunction "2_2") (pintype "input"))
      (node (ref "H1") (pin "1") (pinfunction "1_1") (pintype "unspecified"))
      (node (ref "H2") (pin "1") (pinfunction "1_1") (pintype "unspecified"))
      (node (ref "R23") (pin "1") (pinfunction "1_1") (pintype "input"))
      (node (ref "R28") (pin "1") (pinfunction "1_1") (pintype "input"))
      (node (ref "R3") (pin "2") (pinfunction "2_2") (pintype "input"))
      (node (ref "TP2") (pin "1") (pinfunction "1_1") (pintype "input"))
      (node (ref "U10") (pin "4") (pinfunction "-V_4") (pintype "unspecified"))
      (node (ref "U2") (pin "2") (pinfunction "VOUT(TAB)_2") (pintype "unspecified"))
      (node (ref "U2") (pin "4") (pinfunction "TAB_4") (pintype "unspecified"))
      (node (ref "U3") (pin "3") (pinfunction "VIN_3") (pintype "unspecified"))
      (node (ref "U5") (pin "2") (pinfunction "VCC_2") (pintype "unspecified"))
      (node (ref "U6") (pin "3") (pinfunction "VDDI_3") (pintype "unspecified"))
      (node (ref "U6") (pin "8") (pinfunction "VDDI_8") (pintype "unspecified"))
      (node (ref "U7") (pin "3") (pinfunction "VDDI_3") (pintype "unspecified"))
      (node (ref "U7") (pin "8") (pinfunction "VDDI_8") (pintype "unspecified"))
      (node (ref "U8") (pin "4") (pinfunction "-V_4") (pintype "unspecified"))
      (node (ref "U9") (pin "4") (pinfunction "-V_4") (pintype "unspecified"))
    )
    (net (code "2") (name "+12V") (class "Default")
      (node (ref "C3") (pin "2") (pinfunction "2_2") (pintype "input"))
      (node (ref "C30") (pin "1") (pinfunction "1_1") (pintype "input"))
      (node (ref "C35") (pin "1") (pinfunction "1_1") (pintype "input"))
      (node (ref "C4") (pin "2") (pinfunction "2_2") (pintype "input"))
      (node (ref "C5") (pin "2") (pinfunction "2_2") (pintype "input"))
      (node (ref "C6") (pin "2") (pinfunction "2_2") (pintype "input"))
      (node (ref "D6") (pin "2") (pinfunction "A_2") (pintype "unspecified"))
      (node (ref "D7") (pin "2") (pinfunction "A_2") (pintype "unspecified"))
      (node (ref "L1") (pin "2") (pinfunction "2_2") (pintype "unspecified"))
      (node (ref "R1") (pin "2") (pinfunction "2_2") (pintype "input"))
      (node (ref "TP1") (pin "1") (pinfunction "1_1") (pintype "input"))
      (node (ref "U2") (pin "3") (pinfunction "VIN_3") (pintype "unspecified"))
      (node (ref "U6") (pin "11") (pinfunction "VDDB_11") (pintype "unspecified"))
      (node (ref "U7") (pin "11") (pinfunction "VDDB_11") (pintype "unspecified"))
    )
    (net (code "3") (name "1V65") (class "Default")
      (node (ref "R39") (pin "2") (pinfunction "2_2") (pintype "input"))
      (node (ref "R49") (pin "2") (pinfunction "2_2") (pintype "input"))
      (node (ref "TP10") (pin "1") (pinfunction "1_1") (pintype "input"))
      (node (ref "U10") (pin "1") (pinfunction "OUT_1") (pintype "output"))
      (node (ref "U10") (pin "2") (pinfunction "INVERTING_INPUT_2") (pintype "unspecified"))
    )
    (net (code "4") (name "3V3") (class "Default")
      (node (ref "C12") (pin "2") (pinfunction "2_2") (pintype "input"))
      (node (ref "C13") (pin "2") (pinfunction "2_2") (pintype "input"))
      (node (ref "C14") (pin "2") (pinfunction "2_2") (pintype "input"))
      (node (ref "C15") (pin "2") (pinfunction "2_2") (pintype "input"))
      (node (ref "C8") (pin "2") (pinfunction "2_2") (pintype "input"))
      (node (ref "L2") (pin "1") (pinfunction "1_1") (pintype "unspecified"))
      (node (ref "R10") (pin "2") (pinfunction "2_2") (pintype "input"))
      (node (ref "R11") (pin "2") (pinfunction "2_2") (pintype "input"))
      (node (ref "R4") (pin "1") (pinfunction "1_1") (pintype "input"))
      (node (ref "R51") (pin "1") (pinfunction "1_1") (pintype "input"))
      (node (ref "R53") (pin "1") (pinfunction "1_1") (pintype "input"))
      (node (ref "TP3") (pin "1") (pinfunction "1_1") (pintype "input"))
      (node (ref "U3") (pin "2") (pinfunction "VOUT_2") (pintype "unspecified"))
      (node (ref "U3") (pin "4") (pinfunction "VOUT_4") (pintype "unspecified"))
      (node (ref "U4") (pin "1") (pinfunction "VBAT_1") (pintype "unspecified"))
      (node (ref "U4") (pin "24") (pinfunction "VDD_24") (pintype "unspecified"))
      (node (ref "U4") (pin "36") (pinfunction "VDD_36") (pintype "unspecified"))
      (node (ref "U4") (pin "48") (pinfunction "VDD_48") (pintype "unspecified"))
    )
    (net (code "5") (name "A3V3") (class "Default")
      (node (ref "C11") (pin "1") (pinfunction "1_1") (pintype "input"))
      (node (ref "C9") (pin "2") (pinfunction "2_2") (pintype "input"))
      (node (ref "L2") (pin "2") (pinfunction "2_2") (pintype "unspecified"))
      (node (ref "U4") (pin "9") (pinfunction "VDDA/VREF+_9") (pintype "unspecified"))
    )
    (net (code "6") (name "ADC_IIN") (class "Default")
      (node (ref "C38") (pin "2") (pinfunction "2_2") (pintype "input"))
      (node (ref "R38") (pin "2") (pinfunction "2_2") (pintype "input"))
      (node (ref "U4") (pin "11") (pinfunction "PA1_11") (pintype "unspecified"))
    )
    (net (code "7") (name "ADC_IOUT") (class "Default")
      (node (ref "C41") (pin "2") (pinfunction "2_2") (pintype "input"))
      (node (ref "R48") (pin "2") (pinfunction "2_2") (pintype "input"))
      (node (ref "U4") (pin "13") (pinfunction "PA3_13") (pintype "unspecified"))
    )
    (net (code "8") (name "ADC_VADJ") (class "Default")
      (node (ref "C44") (pin "2") (pinfunction "2_2") (pintype "input"))
      (node (ref "R55") (pin "2") (pinfunction "2_2") (pintype "input"))
      (node (ref "U4") (pin "14") (pinfunction "PA4_14") (pintype "unspecified"))
    )
    (net (code "9") (name "ADC_VIN") (class "Default")
      (node (ref "C37") (pin "2") (pinfunction "2_2") (pintype "input"))
      (node (ref "R35") (pin "2") (pinfunction "2_2") (pintype "input"))
      (node (ref "U4") (pin "10") (pinfunction "PA0_10") (pintype "unspecified"))
    )
    (net (code "10") (name "ADC_VOUT") (class "Default")
      (node (ref "C40") (pin "2") (pinfunction "2_2") (pintype "input"))
      (node (ref "R45") (pin "2") (pinfunction "2_2") (pintype "input"))
      (node (ref "U4") (pin "12") (pinfunction "PA2_12") (pintype "unspecified"))
    )
    (net (code "11") (name "AGND") (class "Default")
      (node (ref "C11") (pin "2") (pinfunction "2_2") (pintype "input"))
      (node (ref "C37") (pin "1") (pinfunction "1_1") (pintype "input"))
      (node (ref "C38") (pin "1") (pinfunction "1_1") (pintype "input"))
      (node (ref "C40") (pin "1") (pinfunction "1_1") (pintype "input"))
      (node (ref "C41") (pin "1") (pinfunction "1_1") (pintype "input"))
      (node (ref "C44") (pin "1") (pinfunction "1_1") (pintype "input"))
      (node (ref "C9") (pin "1") (pinfunction "1_1") (pintype "input"))
      (node (ref "L3") (pin "2") (pinfunction "2_2") (pintype "unspecified"))
      (node (ref "U4") (pin "8") (pinfunction "VSSA/VREF-_8") (pintype "unspecified"))
    )
    (net (code "12") (name "GATE1_H") (class "Default")
      (node (ref "H4") (pin "1") (pinfunction "1_1") (pintype "unspecified"))
      (node (ref "Q1") (pin "4") (pinfunction "G_4") (pintype "unspecified"))
      (node (ref "R16") (pin "1") (pinfunction "1_1") (pintype "input"))
      (node (ref "R24") (pin "2") (pinfunction "2_2") (pintype "input"))
    )
    (net (code "13") (name "GATE1_L") (class "Default")
      (node (ref "H7") (pin "1") (pinfunction "1_1") (pintype "unspecified"))
      (node (ref "Q2") (pin "4") (pinfunction "G_4") (pintype "unspecified"))
      (node (ref "R15") (pin "2") (pinfunction "2_2") (pintype "input"))
      (node (ref "R25") (pin "2") (pinfunction "2_2") (pintype "input"))
    )
    (net (code "14") (name "GATE2_H") (class "Default")
      (node (ref "H10") (pin "1") (pinfunction "1_1") (pintype "unspecified"))
      (node (ref "Q3") (pin "4") (pinfunction "G_4") (pintype "unspecified"))
      (node (ref "R17") (pin "2") (pinfunction "2_2") (pintype "input"))
      (node (ref "R29") (pin "2") (pinfunction "2_2") (pintype "input"))
    )
    (net (code "15") (name "GATE2_L") (class "Default")
      (node (ref "H11") (pin "1") (pinfunction "1_1") (pintype "unspecified"))
      (node (ref "Q4") (pin "4") (pinfunction "G_4") (pintype "unspecified"))
      (node (ref "R18") (pin "1") (pinfunction "1_1") (pintype "input"))
      (node (ref "R30") (pin "2") (pinfunction "2_2") (pintype "input"))
    )
    (net (code "16") (name "GND") (class "Default")
      (node (ref "C1") (pin "1") (pinfunction "1_1") (pintype "input"))
      (node (ref "C10") (pin "1") (pinfunction "1_1") (pintype "input"))
      (node (ref "C12") (pin "1") (pinfunction "1_1") (pintype "input"))
      (node (ref "C13") (pin "1") (pinfunction "1_1") (pintype "input"))
      (node (ref "C14") (pin "1") (pinfunction "1_1") (pintype "input"))
      (node (ref "C15") (pin "1") (pinfunction "1_1") (pintype "input"))
      (node (ref "C16") (pin "1") (pinfunction "1_1") (pintype "input"))
      (node (ref "C17") (pin "1") (pinfunction "1_1") (pintype "input"))
      (node (ref "C18") (pin "1") (pinfunction "1_1") (pintype "input"))
      (node (ref "C19") (pin "1") (pinfunction "1_1") (pintype "input"))
      (node (ref "C2") (pin "1") (pinfunction "1_1") (pintype "input"))
      (node (ref "C20") (pin "2") (pinfunction "2_2") (pintype "input"))
      (node (ref "C21") (pin "2") (pinfunction "2_2") (pintype "input"))
      (node (ref "C22") (pin "2") (pinfunction "2_2") (pintype "input"))
      (node (ref "C23") (pin "2") (pinfunction "2_2") (pintype "input"))
      (node (ref "C24") (pin "1") (pinfunction "1_1") (pintype "input"))
      (node (ref "C25") (pin "1") (pinfunction "1_1") (pintype "input"))
      (node (ref "C26") (pin "2") (pinfunction "2_2") (pintype "input"))
      (node (ref "C27") (pin "2") (pinfunction "2_2") (pintype "input"))
      (node (ref "C28") (pin "1") (pinfunction "1_1") (pintype "input"))
      (node (ref "C30") (pin "2") (pinfunction "2_2") (pintype "input"))
      (node (ref "C31") (pin "2") (pinfunction "2_2") (pintype "input"))
      (node (ref "C32") (pin "2") (pinfunction "2_2") (pintype "input"))
      (node (ref "C33") (pin "1") (pinfunction "1_1") (pintype "input"))
      (node (ref "C35") (pin "2") (pinfunction "2_2") (pintype "input"))
      (node (ref "C36") (pin "2") (pinfunction "2_2") (pintype "input"))
      (node (ref "C39") (pin "2") (pinfunction "2_2") (pintype "input"))
      (node (ref "C4") (pin "1") (pinfunction "1_1") (pintype "input"))
      (node (ref "C42") (pin "1") (pinfunction "1_1") (pintype "input"))
      (node (ref "C43") (pin "2") (pinfunction "2_2") (pintype "input"))
      (node (ref "C5") (pin "1") (pinfunction "1_1") (pintype "input"))
      (node (ref "C6") (pin "1") (pinfunction "1_1") (pintype "input"))
      (node (ref "C7") (pin "1") (pinfunction "1_1") (pintype "input"))
      (node (ref "C8") (pin "1") (pinfunction "1_1") (pintype "input"))
      (node (ref "D3") (pin "2") (pinfunction "A_2") (pintype "unspecified"))
      (node (ref "D4") (pin "2") (pinfunction "A_2") (pintype "unspecified"))
      (node (ref "D5") (pin "2") (pinfunction "A_2") (pintype "unspecified"))
      (node (ref "H1") (pin "4") (pinfunction "4_4") (pintype "unspecified"))
      (node (ref "H12") (pin "1") (pinfunction "1_1") (pintype "unspecified"))
      (node (ref "H2") (pin "4") (pinfunction "4_4") (pintype "unspecified"))
      (node (ref "H8") (pin "1") (pinfunction "1_1") (pintype "unspecified"))
      (node (ref "L3") (pin "1") (pinfunction "1_1") (pintype "unspecified"))
      (node (ref "LED1") (pin "1") (pinfunction "C_1") (pintype "input"))
      (node (ref "LED2") (pin "1") (pinfunction "C_1") (pintype "input"))
      (node (ref "LED3") (pin "1") (pinfunction "C_1") (pintype "input"))
      (node (ref "LED4") (pin "1") (pinfunction "C_1") (pintype "input"))
      (node (ref "LED5") (pin "1") (pinfunction "C_1") (pintype "input"))
      (node (ref "Q2") (pin "1") (pinfunction "S_1") (pintype "unspecified"))
      (node (ref "Q2") (pin "2") (pinfunction "S_2") (pintype "unspecified"))
      (node (ref "Q2") (pin "3") (pinfunction "S_3") (pintype "unspecified"))
      (node (ref "Q4") (pin "1") (pinfunction "S_1") (pintype "unspecified"))
      (node (ref "Q4") (pin "2") (pinfunction "S_2") (pintype "unspecified"))
      (node (ref "Q4") (pin "3") (pinfunction "S_3") (pintype "unspecified"))
      (node (ref "R12") (pin "1") (pinfunction "1_1") (pintype "input"))
      (node (ref "R14") (pin "2") (pinfunction "2_2") (pintype "unspecified"))
      (node (ref "R15") (pin "1") (pinfunction "1_1") (pintype "input"))
      (node (ref "R18") (pin "2") (pinfunction "2_2") (pintype "input"))
      (node (ref "R19") (pin "1") (pinfunction "1_1") (pintype "input"))
      (node (ref "R2") (pin "1") (pinfunction "1_1") (pintype "input"))
      (node (ref "R20") (pin "1") (pinfunction "1_1") (pintype "unspecified"))
      (node (ref "R21") (pin "2") (pinfunction "2_2") (pintype "input"))
      (node (ref "R22") (pin "2") (pinfunction "2_2") (pintype "input"))
      (node (ref "R26") (pin "2") (pinfunction "2_2") (pintype "input"))
      (node (ref "R27") (pin "2") (pinfunction "2_2") (pintype "input"))
      (node (ref "R31") (pin "2") (pinfunction "2_2") (pintype "input"))
      (node (ref "R36") (pin "1") (pinfunction "1_1") (pintype "input"))
      (node (ref "R41") (pin "2") (pinfunction "2_2") (pintype "input"))
      (node (ref "R47") (pin "1") (pinfunction "1_1") (pintype "input"))
      (node (ref "R5") (pin "2") (pinfunction "2_2") (pintype "input"))
      (node (ref "R52") (pin "1") (pinfunction "1_1") (pintype "input"))
      (node (ref "R54") (pin "1") (pinfunction "1_1") (pintype "input"))
      (node (ref "R54") (pin "2") (pinfunction "2_2") (pintype "input"))
      (node (ref "SW1") (pin "1") (pinfunction "1_1") (pintype "unspecified"))
      (node (ref "SW2") (pin "1") (pinfunction "1_1") (pintype "unspecified"))
      (node (ref "TP5") (pin "1") (pinfunction "1_1") (pintype "input"))
      (node (ref "U1") (pin "5") (pinfunction "GND_5") (pintype "unspecified"))
      (node (ref "U1") (pin "6") (pinfunction "GND_6") (pintype "unspecified"))
      (node (ref "U1") (pin "7") (pinfunction "GND_7") (pintype "unspecified"))
      (node (ref "U1") (pin "8") (pinfunction "GND_8") (pintype "unspecified"))
      (node (ref "U1") (pin "9") (pinfunction "9_9") (pintype "unspecified"))
      (node (ref "U10") (pin "8") (pinfunction "+V_8") (pintype "unspecified"))
      (node (ref "U2") (pin "1") (pinfunction "ADJ(GND)_1") (pintype "unspecified"))
      (node (ref "U3") (pin "1") (pinfunction "GND_1") (pintype "unspecified"))
      (node (ref "U4") (pin "23") (pinfunction "VSS_23") (pintype "unspecified"))
      (node (ref "U4") (pin "35") (pinfunction "VSS_35") (pintype "unspecified"))
      (node (ref "U4") (pin "47") (pinfunction "VSS_47") (pintype "unspecified"))
      (node (ref "U5") (pin "1") (pinfunction "GND_1") (pintype "unspecified"))
      (node (ref "U6") (pin "4") (pinfunction "GNDI_4") (pintype "unspecified"))
      (node (ref "U6") (pin "5") (pinfunction "DISABLE_5") (pintype "unspecified"))
      (node (ref "U6") (pin "9") (pinfunction "GNDB_9") (pintype "unspecified"))
      (node (ref "U7") (pin "4") (pinfunction "GNDI_4") (pintype "unspecified"))
      (node (ref "U7") (pin "5") (pinfunction "DISABLE_5") (pintype "unspecified"))
      (node (ref "U7") (pin "9") (pinfunction "GNDB_9") (pintype "unspecified"))
      (node (ref "U8") (pin "8") (pinfunction "+V_8") (pintype "unspecified"))
      (node (ref "U9") (pin "8") (pinfunction "+V_8") (pintype "unspecified"))
    )
    (net (code "17") (name "HS-1") (class "Default")
      (node (ref "C29") (pin "2") (pinfunction "2_2") (pintype "input"))
      (node (ref "H3") (pin "1") (pinfunction "1_1") (pintype "unspecified"))
      (node (ref "L4") (pin "1") (pinfunction "1_1") (pintype "unspecified"))
      (node (ref "Q1") (pin "1") (pinfunction "S_1") (pintype "unspecified"))
      (node (ref "Q1") (pin "2") (pinfunction "S_2") (pintype "unspecified"))
      (node (ref "Q1") (pin "3") (pinfunction "S_3") (pintype "unspecified"))
      (node (ref "Q2") (pin "5") (pinfunction "D_5") (pintype "unspecified"))
      (node (ref "Q2") (pin "6") (pinfunction "D_6") (pintype "unspecified"))
      (node (ref "Q2") (pin "7") (pinfunction "D_7") (pintype "unspecified"))
      (node (ref "Q2") (pin "8") (pinfunction "D_8") (pintype "unspecified"))
      (node (ref "R16") (pin "2") (pinfunction "2_2") (pintype "input"))
      (node (ref "U6") (pin "14") (pinfunction "GNDA_14") (pintype "unspecified"))
    )
    (net (code "18") (name "HS-2") (class "Default")
      (node (ref "C34") (pin "2") (pinfunction "2_2") (pintype "input"))
      (node (ref "H9") (pin "1") (pinfunction "1_1") (pintype "unspecified"))
      (node (ref "L4") (pin "2") (pinfunction "2_2") (pintype "unspecified"))
      (node (ref "Q3") (pin "1") (pinfunction "S_1") (pintype "unspecified"))
      (node (ref "Q3") (pin "2") (pinfunction "S_2") (pintype "unspecified"))
      (node (ref "Q3") (pin "3") (pinfunction "S_3") (pintype "unspecified"))
      (node (ref "Q4") (pin "5") (pinfunction "D_5") (pintype "unspecified"))
      (node (ref "Q4") (pin "6") (pinfunction "D_6") (pintype "unspecified"))
      (node (ref "Q4") (pin "7") (pinfunction "D_7") (pintype "unspecified"))
      (node (ref "Q4") (pin "8") (pinfunction "D_8") (pintype "unspecified"))
      (node (ref "R17") (pin "1") (pinfunction "1_1") (pintype "input"))
      (node (ref "U7") (pin "14") (pinfunction "GNDA_14") (pintype "unspecified"))
    )
    (net (code "19") (name "I2C_SCL") (class "Default")
      (node (ref "U4") (pin "45") (pinfunction "PB8_45") (pintype "unspecified"))
      (node (ref "U5") (pin "3") (pinfunction "SCL_3") (pintype "unspecified"))
    )
    (net (code "20") (name "I2C_SDA") (class "Default")
      (node (ref "U4") (pin "46") (pinfunction "PB9_46") (pintype "unspecified"))
      (node (ref "U5") (pin "4") (pinfunction "SDA_4") (pintype "unspecified"))
    )
    (net (code "21") (name "KEY1") (class "Default")
      (node (ref "C16") (pin "2") (pinfunction "2_2") (pintype "input"))
      (node (ref "R10") (pin "1") (pinfunction "1_1") (pintype "input"))
      (node (ref "SW1") (pin "3") (pinfunction "3_3") (pintype "unspecified"))
      (node (ref "U4") (pin "39") (pinfunction "PB3_39") (pintype "unspecified"))
    )
    (net (code "22") (name "KEY2") (class "Default")
      (node (ref "C17") (pin "2") (pinfunction "2_2") (pintype "input"))
      (node (ref "R11") (pin "1") (pinfunction "1_1") (pintype "input"))
      (node (ref "SW2") (pin "3") (pinfunction "3_3") (pintype "unspecified"))
      (node (ref "U4") (pin "40") (pinfunction "PB4_40") (pintype "unspecified"))
    )
    (net (code "23") (name "LED_G") (class "Default")
      (node (ref "R8") (pin "2") (pinfunction "2_2") (pintype "input"))
      (node (ref "U4") (pin "18") (pinfunction "PB0_18") (pintype "unspecified"))
    )
    (net (code "24") (name "LED_R") (class "Default")
      (node (ref "R6") (pin "2") (pinfunction "2_2") (pintype "input"))
      (node (ref "U4") (pin "20") (pinfunction "PB2_20") (pintype "unspecified"))
    )
    (net (code "25") (name "LED_Y") (class "Default")
      (node (ref "R7") (pin "2") (pinfunction "2_2") (pintype "input"))
      (node (ref "U4") (pin "19") (pinfunction "PB1_19") (pintype "unspecified"))
    )
    (net (code "26") (name "Net-(D1-K)") (class "Default")
      (node (ref "C1") (pin "2") (pinfunction "2_2") (pintype "input"))
      (node (ref "C2") (pin "2") (pinfunction "2_2") (pintype "input"))
      (node (ref "D1") (pin "1") (pinfunction "K_1") (pintype "unspecified"))
      (node (ref "D2") (pin "1") (pinfunction "K_1") (pintype "unspecified"))
      (node (ref "TP4") (pin "1") (pinfunction "1_1") (pintype "input"))
      (node (ref "U1") (pin "1") (pinfunction "VIN_1") (pintype "unspecified"))
    )
    (net (code "27") (name "Net-(D3-K)") (class "Default")
      (node (ref "D3") (pin "1") (pinfunction "K_1") (pintype "unspecified"))
      (node (ref "L1") (pin "1") (pinfunction "1_1") (pintype "unspecified"))
      (node (ref "U1") (pin "2") (pinfunction "SW_2") (pintype "unspecified"))
    )
    (net (code "28") (name "Net-(D6-K)") (class "Default")
      (node (ref "C29") (pin "1") (pinfunction "1_1") (pintype "input"))
      (node (ref "D6") (pin "1") (pinfunction "K_1") (pintype "unspecified"))
      (node (ref "U6") (pin "16") (pinfunction "VDDA_16") (pintype "unspecified"))
    )
    (net (code "29") (name "Net-(D7-K)") (class "Default")
      (node (ref "C34") (pin "1") (pinfunction "1_1") (pintype "input"))
      (node (ref "D7") (pin "1") (pinfunction "K_1") (pintype "unspecified"))
      (node (ref "U7") (pin "16") (pinfunction "VDDA_16") (pintype "unspecified"))
    )
    (net (code "30") (name "Net-(LED1-A)") (class "Default")
      (node (ref "LED1") (pin "2") (pinfunction "A_2") (pintype "input"))
      (node (ref "R3") (pin "1") (pinfunction "1_1") (pintype "input"))
    )
    (net (code "31") (name "Net-(LED2-A)") (class "Default")
      (node (ref "LED2") (pin "2") (pinfunction "A_2") (pintype "input"))
      (node (ref "R6") (pin "1") (pinfunction "1_1") (pintype "input"))
    )
    (net (code "32") (name "Net-(LED3-A)") (class "Default")
      (node (ref "LED3") (pin "2") (pinfunction "A_2") (pintype "input"))
      (node (ref "R7") (pin "1") (pinfunction "1_1") (pintype "input"))
    )
    (net (code "33") (name "Net-(LED4-A)") (class "Default")
      (node (ref "LED4") (pin "2") (pinfunction "A_2") (pintype "input"))
      (node (ref "R8") (pin "1") (pinfunction "1_1") (pintype "input"))
    )
    (net (code "34") (name "Net-(LED5-A)") (class "Default")
      (node (ref "LED5") (pin "2") (pinfunction "A_2") (pintype "input"))
      (node (ref "R9") (pin "1") (pinfunction "1_1") (pintype "input"))
    )
    (net (code "35") (name "Net-(R53-Pad2)") (class "Default")
      (node (ref "R53") (pin "2") (pinfunction "2_2") (pintype "input"))
      (node (ref "R54") (pin "3") (pinfunction "3_3") (pintype "input"))
      (node (ref "R55") (pin "1") (pinfunction "1_1") (pintype "input"))
    )
    (net (code "36") (name "Net-(U1-FB)") (class "Default")
      (node (ref "C3") (pin "1") (pinfunction "1_1") (pintype "input"))
      (node (ref "R1") (pin "1") (pinfunction "1_1") (pintype "input"))
      (node (ref "R2") (pin "2") (pinfunction "2_2") (pintype "input"))
      (node (ref "U1") (pin "3") (pinfunction "FB_3") (pintype "unspecified"))
    )
    (net (code "37") (name "Net-(U4-BOOT0)") (class "Default")
      (node (ref "R5") (pin "1") (pinfunction "1_1") (pintype "input"))
      (node (ref "U4") (pin "44") (pinfunction "BOOT0_44") (pintype "unspecified"))
    )
    (net (code "38") (name "Net-(U4-NRST)") (class "Default")
      (node (ref "C10") (pin "2") (pinfunction "2_2") (pintype "input"))
      (node (ref "R4") (pin "2") (pinfunction "2_2") (pintype "input"))
      (node (ref "U4") (pin "7") (pinfunction "NRST_7") (pintype "unspecified"))
    )
    (net (code "39") (name "Net-(U6-DT)") (class "Default")
      (node (ref "R23") (pin "2") (pinfunction "2_2") (pintype "input"))
      (node (ref "U6") (pin "6") (pinfunction "DT_6") (pintype "unspecified"))
    )
    (net (code "40") (name "Net-(U6-VOA)") (class "Default")
      (node (ref "R24") (pin "1") (pinfunction "1_1") (pintype "input"))
      (node (ref "U6") (pin "15") (pinfunction "VOA_15") (pintype "unspecified"))
    )
    (net (code "41") (name "Net-(U6-VOB)") (class "Default")
      (node (ref "R25") (pin "1") (pinfunction "1_1") (pintype "input"))
      (node (ref "U6") (pin "10") (pinfunction "VOB_10") (pintype "unspecified"))
    )
    (net (code "42") (name "Net-(U7-DT)") (class "Default")
      (node (ref "R28") (pin "2") (pinfunction "2_2") (pintype "input"))
      (node (ref "U7") (pin "6") (pinfunction "DT_6") (pintype "unspecified"))
    )
    (net (code "43") (name "Net-(U7-VOA)") (class "Default")
      (node (ref "R29") (pin "1") (pinfunction "1_1") (pintype "input"))
      (node (ref "U7") (pin "15") (pinfunction "VOA_15") (pintype "unspecified"))
    )
    (net (code "44") (name "Net-(U7-VOB)") (class "Default")
      (node (ref "R30") (pin "1") (pinfunction "1_1") (pintype "input"))
      (node (ref "U7") (pin "10") (pinfunction "VOB_10") (pintype "unspecified"))
    )
    (net (code "45") (name "Net-(U8A-INVERTING_INPUT)") (class "Default")
      (node (ref "R32") (pin "2") (pinfunction "2_2") (pintype "input"))
      (node (ref "R34") (pin "2") (pinfunction "2_2") (pintype "input"))
      (node (ref "U8") (pin "2") (pinfunction "INVERTING_INPUT_2") (pintype "unspecified"))
    )
    (net (code "46") (name "Net-(U8A-NONINVERTING_INPUT)") (class "Default")
      (node (ref "R31") (pin "1") (pinfunction "1_1") (pintype "input"))
      (node (ref "R33") (pin "2") (pinfunction "2_2") (pintype "input"))
      (node (ref "U8") (pin "3") (pinfunction "NONINVERTING_INPUT_3") (pintype "unspecified"))
    )
    (net (code "47") (name "Net-(U8A-OUT)") (class "Default")
      (node (ref "R32") (pin "1") (pinfunction "1_1") (pintype "input"))
      (node (ref "R35") (pin "1") (pinfunction "1_1") (pintype "input"))
      (node (ref "U8") (pin "1") (pinfunction "OUT_1") (pintype "output"))
    )
    (net (code "48") (name "Net-(U8B-INVERTING_INPUT)") (class "Default")
      (node (ref "R37") (pin "2") (pinfunction "2_2") (pintype "input"))
      (node (ref "R40") (pin "2") (pinfunction "2_2") (pintype "input"))
      (node (ref "U8") (pin "6") (pinfunction "INVERTING_INPUT_6") (pintype "unspecified"))
    )
    (net (code "49") (name "Net-(U8B-NONINVERTING_INPUT)") (class "Default")
      (node (ref "R36") (pin "2") (pinfunction "2_2") (pintype "input"))
      (node (ref "R39") (pin "1") (pinfunction "1_1") (pintype "input"))
      (node (ref "U8") (pin "5") (pinfunction "NONINVERTING_INPUT_5") (pintype "unspecified"))
    )
    (net (code "50") (name "Net-(U8B-OUT)") (class "Default")
      (node (ref "R38") (pin "1") (pinfunction "1_1") (pintype "input"))
      (node (ref "R40") (pin "1") (pinfunction "1_1") (pintype "input"))
      (node (ref "U8") (pin "7") (pinfunction "OUT_7") (pintype "output"))
    )
    (net (code "51") (name "Net-(U9A-INVERTING_INPUT)") (class "Default")
      (node (ref "R42") (pin "2") (pinfunction "2_2") (pintype "input"))
      (node (ref "R44") (pin "2") (pinfunction "2_2") (pintype "input"))
      (node (ref "U9") (pin "2") (pinfunction "INVERTING_INPUT_2") (pintype "unspecified"))
    )
    (net (code "52") (name "Net-(U9A-NONINVERTING_INPUT)") (class "Default")
      (node (ref "R41") (pin "1") (pinfunction "1_1") (pintype "input"))
      (node (ref "R43") (pin "2") (pinfunction "2_2") (pintype "input"))
      (node (ref "U9") (pin "3") (pinfunction "NONINVERTING_INPUT_3") (pintype "unspecified"))
    )
    (net (code "53") (name "Net-(U9A-OUT)") (class "Default")
      (node (ref "R42") (pin "1") (pinfunction "1_1") (pintype "input"))
      (node (ref "R45") (pin "1") (pinfunction "1_1") (pintype "input"))
      (node (ref "U9") (pin "1") (pinfunction "OUT_1") (pintype "output"))
    )
    (net (code "54") (name "Net-(U9B-INVERTING_INPUT)") (class "Default")
      (node (ref "R47") (pin "2") (pinfunction "2_2") (pintype "input"))
      (node (ref "R50") (pin "2") (pinfunction "2_2") (pintype "input"))
      (node (ref "U9") (pin "6") (pinfunction "INVERTING_INPUT_6") (pintype "unspecified"))
    )
    (net (code "55") (name "Net-(U9B-NONINVERTING_INPUT)") (class "Default")
      (node (ref "R46") (pin "2") (pinfunction "2_2") (pintype "input"))
      (node (ref "R49") (pin "1") (pinfunction "1_1") (pintype "input"))
      (node (ref "U9") (pin "5") (pinfunction "NONINVERTING_INPUT_5") (pintype "unspecified"))
    )
    (net (code "56") (name "Net-(U9B-OUT)") (class "Default")
      (node (ref "R48") (pin "1") (pinfunction "1_1") (pintype "input"))
      (node (ref "R50") (pin "1") (pinfunction "1_1") (pintype "input"))
      (node (ref "U9") (pin "7") (pinfunction "OUT_7") (pintype "output"))
    )
    (net (code "57") (name "Net-(U10A-NONINVERTING_INPUT)") (class "Default")
      (node (ref "C42") (pin "2") (pinfunction "2_2") (pintype "input"))
      (node (ref "R51") (pin "2") (pinfunction "2_2") (pintype "input"))
      (node (ref "R52") (pin "2") (pinfunction "2_2") (pintype "input"))
      (node (ref "U10") (pin "3") (pinfunction "NONINVERTING_INPUT_3") (pintype "unspecified"))
    )
    (net (code "58") (name "PC13") (class "Default")
      (node (ref "R9") (pin "2") (pinfunction "2_2") (pintype "input"))
      (node (ref "U4") (pin "2") (pinfunction "PC13_2") (pintype "unspecified"))
    )
    (net (code "59") (name "PWM1H") (class "Default")
      (node (ref "C26") (pin "1") (pinfunction "1_1") (pintype "input"))
      (node (ref "R21") (pin "1") (pinfunction "1_1") (pintype "input"))
      (node (ref "U4") (pin "29") (pinfunction "PA8_29") (pintype "unspecified"))
      (node (ref "U6") (pin "1") (pinfunction "VIA_1") (pintype "unspecified"))
    )
    (net (code "60") (name "PWM1L") (class "Default")
      (node (ref "C27") (pin "1") (pinfunction "1_1") (pintype "input"))
      (node (ref "R22") (pin "1") (pinfunction "1_1") (pintype "input"))
      (node (ref "U4") (pin "30") (pinfunction "PA9_30") (pintype "unspecified"))
      (node (ref "U6") (pin "2") (pinfunction "VIB_2") (pintype "unspecified"))
    )
    (net (code "61") (name "PWM2H") (class "Default")
      (node (ref "C31") (pin "1") (pinfunction "1_1") (pintype "input"))
      (node (ref "R26") (pin "1") (pinfunction "1_1") (pintype "input"))
      (node (ref "U4") (pin "31") (pinfunction "PA10_31") (pintype "unspecified"))
      (node (ref "U7") (pin "1") (pinfunction "VIA_1") (pintype "unspecified"))
    )
    (net (code "62") (name "PWML2") (class "Default")
      (node (ref "C32") (pin "1") (pinfunction "1_1") (pintype "input"))
      (node (ref "R27") (pin "1") (pinfunction "1_1") (pintype "input"))
      (node (ref "U4") (pin "32") (pinfunction "PA11_32") (pintype "unspecified"))
      (node (ref "U7") (pin "2") (pinfunction "VIB_2") (pintype "unspecified"))
    )
    (net (code "63") (name "RX") (class "Default")
      (node (ref "H1") (pin "3") (pinfunction "3_3") (pintype "unspecified"))
      (node (ref "U4") (pin "43") (pinfunction "PB7_43") (pintype "unspecified"))
    )
    (net (code "64") (name "SWCLK") (class "Default")
      (node (ref "H2") (pin "2") (pinfunction "2_2") (pintype "unspecified"))
      (node (ref "U4") (pin "37") (pinfunction "PA14_37") (pintype "unspecified"))
    )
    (net (code "65") (name "SWDAT") (class "Default")
      (node (ref "H2") (pin "3") (pinfunction "3_3") (pintype "unspecified"))
      (node (ref "U4") (pin "34") (pinfunction "PA13_34") (pintype "unspecified"))
    )
    (net (code "66") (name "TX") (class "Default")
      (node (ref "H1") (pin "2") (pinfunction "2_2") (pintype "unspecified"))
      (node (ref "U4") (pin "42") (pinfunction "PB6_42") (pintype "unspecified"))
    )
    (net (code "67") (name "VIN+") (class "Default")
      (node (ref "C18") (pin "2") (pinfunction "2_2") (pintype "input"))
      (node (ref "C19") (pin "2") (pinfunction "2_2") (pintype "input"))
      (node (ref "C20") (pin "1") (pinfunction "1_1") (pintype "input"))
      (node (ref "C21") (pin "1") (pinfunction "1_1") (pintype "input"))
      (node (ref "D2") (pin "2") (pinfunction "A_2") (pintype "unspecified"))
      (node (ref "D4") (pin "1") (pinfunction "K_1") (pintype "unspecified"))
      (node (ref "P1") (pin "1") (pinfunction "1_1") (pintype "unspecified"))
      (node (ref "P1") (pin "2") (pinfunction "2_2") (pintype "unspecified"))
      (node (ref "Q1") (pin "5") (pinfunction "D_5") (pintype "unspecified"))
      (node (ref "Q1") (pin "6") (pinfunction "D_6") (pintype "unspecified"))
      (node (ref "Q1") (pin "7") (pinfunction "D_7") (pintype "unspecified"))
      (node (ref "Q1") (pin "8") (pinfunction "D_8") (pintype "unspecified"))
      (node (ref "R12") (pin "2") (pinfunction "2_2") (pintype "input"))
      (node (ref "R33") (pin "1") (pinfunction "1_1") (pintype "input"))
      (node (ref "TP6") (pin "1") (pinfunction "1_1") (pintype "input"))
    )
    (net (code "68") (name "VIN-") (class "Default")
      (node (ref "P2") (pin "1") (pinfunction "1_1") (pintype "unspecified"))
      (node (ref "P2") (pin "2") (pinfunction "2_2") (pintype "unspecified"))
      (node (ref "R14") (pin "1") (pinfunction "1_1") (pintype "unspecified"))
      (node (ref "R34") (pin "1") (pinfunction "1_1") (pintype "input"))
      (node (ref "R37") (pin "1") (pinfunction "1_1") (pintype "input"))
      (node (ref "TP7") (pin "1") (pinfunction "1_1") (pintype "input"))
    )
    (net (code "69") (name "VOUT+") (class "Default")
      (node (ref "C22") (pin "1") (pinfunction "1_1") (pintype "input"))
      (node (ref "C23") (pin "1") (pinfunction "1_1") (pintype "input"))
      (node (ref "C24") (pin "2") (pinfunction "2_2") (pintype "input"))
      (node (ref "C25") (pin "2") (pinfunction "2_2") (pintype "input"))
      (node (ref "D1") (pin "2") (pinfunction "A_2") (pintype "unspecified"))
      (node (ref "D5") (pin "1") (pinfunction "K_1") (pintype "unspecified"))
      (node (ref "P3") (pin "1") (pinfunction "1_1") (pintype "unspecified"))
      (node (ref "P3") (pin "2") (pinfunction "2_2") (pintype "unspecified"))
      (node (ref "Q3") (pin "5") (pinfunction "D_5") (pintype "unspecified"))
      (node (ref "Q3") (pin "6") (pinfunction "D_6") (pintype "unspecified"))
      (node (ref "Q3") (pin "7") (pinfunction "D_7") (pintype "unspecified"))
      (node (ref "Q3") (pin "8") (pinfunction "D_8") (pintype "unspecified"))
      (node (ref "R19") (pin "2") (pinfunction "2_2") (pintype "input"))
      (node (ref "R43") (pin "1") (pinfunction "1_1") (pintype "input"))
    )
    (net (code "70") (name "VOUT-") (class "Default")
      (node (ref "P4") (pin "1") (pinfunction "1_1") (pintype "unspecified"))
      (node (ref "P4") (pin "2") (pinfunction "2_2") (pintype "unspecified"))
      (node (ref "R20") (pin "2") (pinfunction "2_2") (pintype "unspecified"))
      (node (ref "R44") (pin "1") (pinfunction "1_1") (pintype "input"))
      (node (ref "R46") (pin "1") (pinfunction "1_1") (pintype "input"))
    )
    (net (code "71") (name "unconnected-(M1-Pad1)") (class "Default")
      (node (ref "M1") (pin "1") (pinfunction "1_1") (pintype "unspecified+no_connect"))
    )
    (net (code "72") (name "unconnected-(M2-Pad1)") (class "Default")
      (node (ref "M2") (pin "1") (pinfunction "1_1") (pintype "unspecified+no_connect"))
    )
    (net (code "73") (name "unconnected-(M3-Pad1)") (class "Default")
      (node (ref "M3") (pin "1") (pinfunction "1_1") (pintype "unspecified+no_connect"))
    )
    (net (code "74") (name "unconnected-(M4-Pad1)") (class "Default")
      (node (ref "M4") (pin "1") (pinfunction "1_1") (pintype "unspecified+no_connect"))
    )
    (net (code "75") (name "unconnected-(SW1-Pad2)") (class "Default")
      (node (ref "SW1") (pin "2") (pinfunction "2_2") (pintype "unspecified+no_connect"))
    )
    (net (code "76") (name "unconnected-(SW1-Pad4)") (class "Default")
      (node (ref "SW1") (pin "4") (pinfunction "4_4") (pintype "unspecified+no_connect"))
    )
    (net (code "77") (name "unconnected-(SW2-Pad2)") (class "Default")
      (node (ref "SW2") (pin "2") (pinfunction "2_2") (pintype "unspecified+no_connect"))
    )
    (net (code "78") (name "unconnected-(SW2-Pad4)") (class "Default")
      (node (ref "SW2") (pin "4") (pinfunction "4_4") (pintype "unspecified+no_connect"))
    )
    (net (code "79") (name "unconnected-(U1-EN-Pad4)") (class "Default")
      (node (ref "U1") (pin "4") (pinfunction "EN_4") (pintype "unspecified+no_connect"))
    )
    (net (code "80") (name "unconnected-(U4-PA5-Pad15)") (class "Default")
      (node (ref "U4") (pin "15") (pinfunction "PA5_15") (pintype "unspecified+no_connect"))
    )
    (net (code "81") (name "unconnected-(U4-PA6-Pad16)") (class "Default")
      (node (ref "U4") (pin "16") (pinfunction "PA6_16") (pintype "unspecified+no_connect"))
    )
    (net (code "82") (name "unconnected-(U4-PA7-Pad17)") (class "Default")
      (node (ref "U4") (pin "17") (pinfunction "PA7_17") (pintype "unspecified+no_connect"))
    )
    (net (code "83") (name "unconnected-(U4-PA12-Pad33)") (class "Default")
      (node (ref "U4") (pin "33") (pinfunction "PA12_33") (pintype "unspecified+no_connect"))
    )
    (net (code "84") (name "unconnected-(U4-PA15-Pad38)") (class "Default")
      (node (ref "U4") (pin "38") (pinfunction "PA15_38") (pintype "unspecified+no_connect"))
    )
    (net (code "85") (name "unconnected-(U4-PB5-Pad41)") (class "Default")
      (node (ref "U4") (pin "41") (pinfunction "PB5_41") (pintype "unspecified+no_connect"))
    )
    (net (code "86") (name "unconnected-(U4-PB10-Pad21)") (class "Default")
      (node (ref "U4") (pin "21") (pinfunction "PB10_21") (pintype "unspecified+no_connect"))
    )
    (net (code "87") (name "unconnected-(U4-PB11-Pad22)") (class "Default")
      (node (ref "U4") (pin "22") (pinfunction "PB11_22") (pintype "unspecified+no_connect"))
    )
    (net (code "88") (name "unconnected-(U4-PB12-Pad25)") (class "Default")
      (node (ref "U4") (pin "25") (pinfunction "PB12_25") (pintype "unspecified+no_connect"))
    )
    (net (code "89") (name "unconnected-(U4-PB13-Pad26)") (class "Default")
      (node (ref "U4") (pin "26") (pinfunction "PB13_26") (pintype "unspecified+no_connect"))
    )
    (net (code "90") (name "unconnected-(U4-PB14-Pad27)") (class "Default")
      (node (ref "U4") (pin "27") (pinfunction "PB14_27") (pintype "unspecified+no_connect"))
    )
    (net (code "91") (name "unconnected-(U4-PB15-Pad28)") (class "Default")
      (node (ref "U4") (pin "28") (pinfunction "PB15_28") (pintype "unspecified+no_connect"))
    )
    (net (code "92") (name "unconnected-(U4-PC14{slash}OSC32_IN-Pad3)") (class "Default")
      (node (ref "U4") (pin "3") (pinfunction "PC14/OSC32_IN_3") (pintype "unspecified+no_connect"))
    )
    (net (code "93") (name "unconnected-(U4-PC15{slash}OSC32_OUT-Pad4)") (class "Default")
      (node (ref "U4") (pin "4") (pinfunction "PC15/OSC32_OUT_4") (pintype "unspecified+no_connect"))
    )
    (net (code "94") (name "unconnected-(U4-PF0{slash}OSC_IN-Pad5)") (class "Default")
      (node (ref "U4") (pin "5") (pinfunction "PF0/OSC_IN_5") (pintype "unspecified+no_connect"))
    )
    (net (code "95") (name "unconnected-(U4-PF1{slash}OSC_OUT-Pad6)") (class "Default")
      (node (ref "U4") (pin "6") (pinfunction "PF1/OSC_OUT_6") (pintype "unspecified+no_connect"))
    )
    (net (code "96") (name "unconnected-(U6-NC-Pad7)") (class "Default")
      (node (ref "U6") (pin "7") (pinfunction "NC_7") (pintype "unspecified+no_connect"))
    )
    (net (code "97") (name "unconnected-(U6-NC-Pad12)") (class "Default")
      (node (ref "U6") (pin "12") (pinfunction "NC_12") (pintype "unspecified+no_connect"))
    )
    (net (code "98") (name "unconnected-(U6-NC-Pad13)") (class "Default")
      (node (ref "U6") (pin "13") (pinfunction "NC_13") (pintype "unspecified+no_connect"))
    )
    (net (code "99") (name "unconnected-(U7-NC-Pad7)") (class "Default")
      (node (ref "U7") (pin "7") (pinfunction "NC_7") (pintype "unspecified+no_connect"))
    )
    (net (code "100") (name "unconnected-(U7-NC-Pad12)") (class "Default")
      (node (ref "U7") (pin "12") (pinfunction "NC_12") (pintype "unspecified+no_connect"))
    )
    (net (code "101") (name "unconnected-(U7-NC-Pad13)") (class "Default")
      (node (ref "U7") (pin "13") (pinfunction "NC_13") (pintype "unspecified+no_connect"))
    )
  )
)
